# MCU.net
KiCad netlist of a schematic drawn in Altium Designer
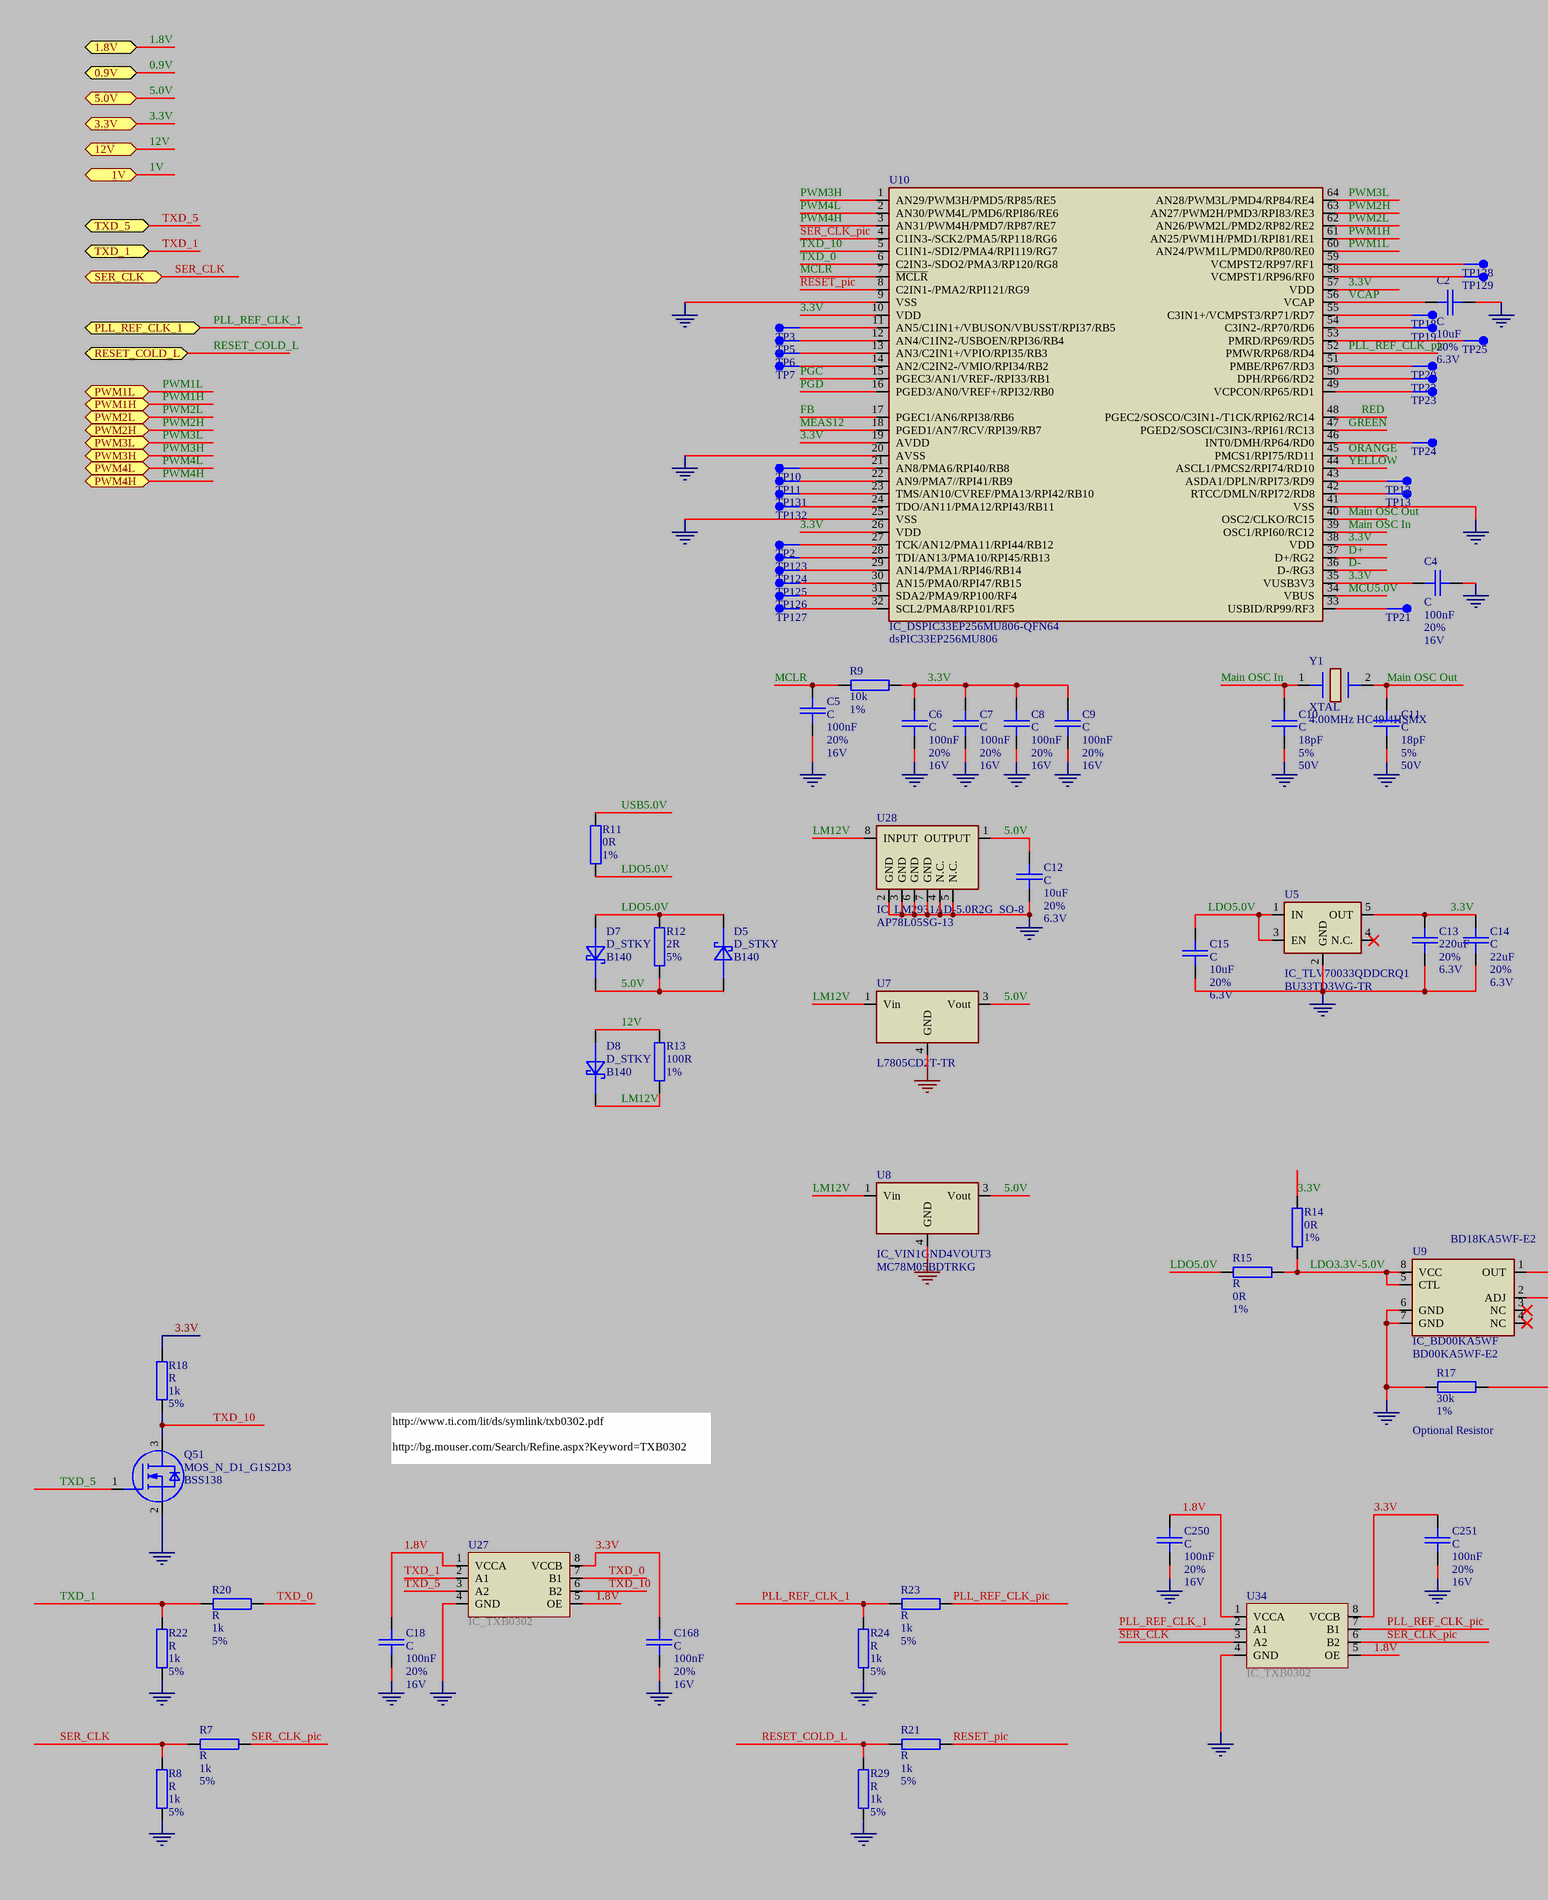
[diagram p0: MCU.SchDoc, left]
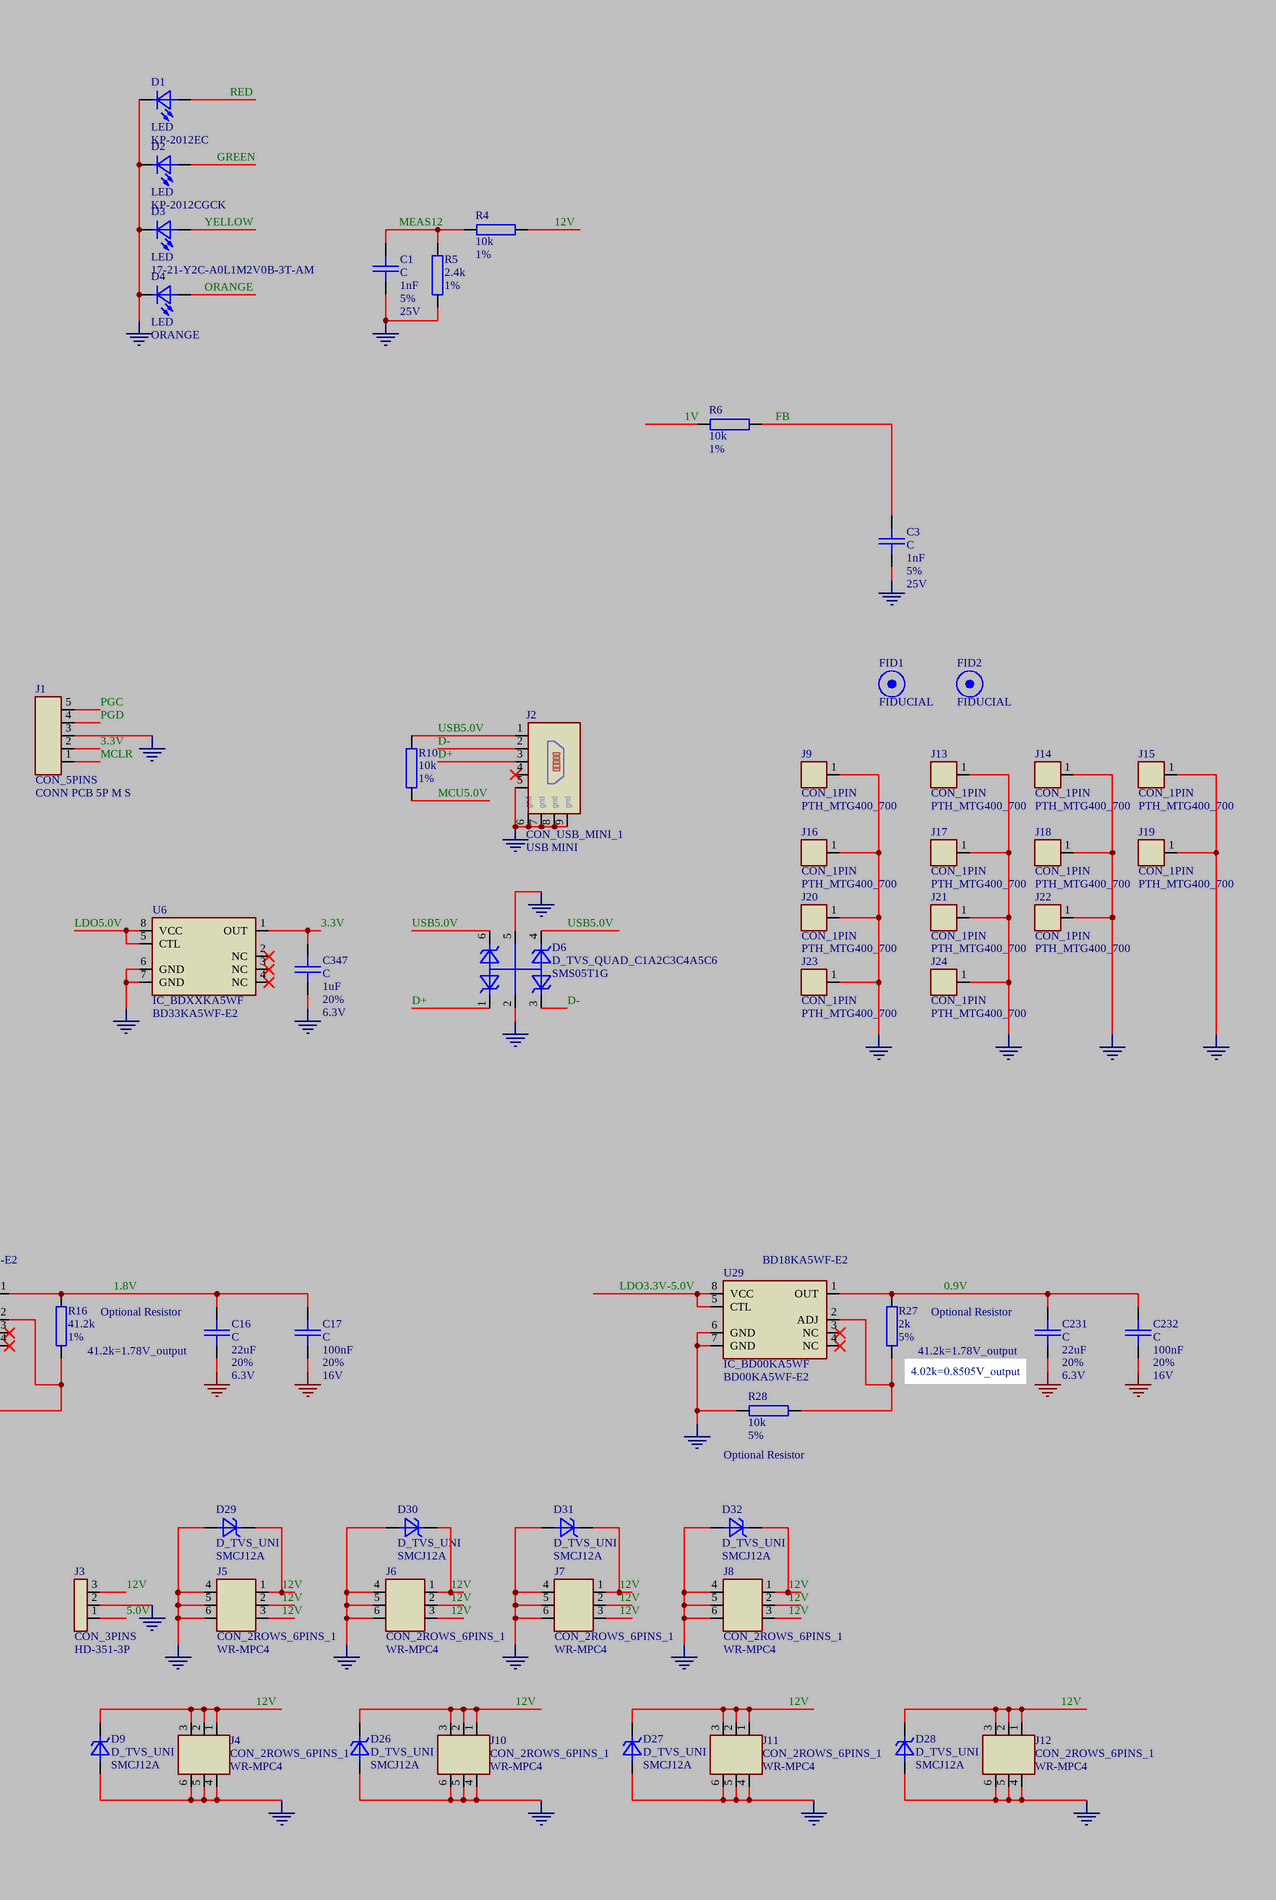
[diagram p1: MCU.SchDoc, right]

(export (version "E")
  (design (tool "Eeschema 10.0.6"))
  (components
    (comp (ref "C1")
      (value "C")
      (footprint "SMD_0603_CAPC1608X95N")
      (fields
        (field (name "DB_PART_NUMBER") "CAP000024113")
        (field (name "DB_VALUE") "1nF")
        (field (name "DB_TOLERANCE") "5%")
        (field (name "DB_VOLTAGE") "25V")
        (field (name "DB_MANUFACTURER_PART") "KEMET    C0603C102J3RAC")
      )
      (libsource (lib "Database_Libs1") (part "C"))
    )
    (comp (ref "C2")
      (value "C")
      (footprint "SMD_0603_CAPC1608X95N")
      (fields
        (field (name "DB_PART_NUMBER") "CAP000043646")
        (field (name "DB_VALUE") "10uF")
        (field (name "DB_TOLERANCE") "20%")
        (field (name "DB_VOLTAGE") "6.3V")
        (field (name "DB_MANUFACTURER_PART") "KEMET    C0603C106M9PAC")
      )
      (libsource (lib "Database_Libs1") (part "C"))
    )
    (comp (ref "C3")
      (value "C")
      (footprint "SMD_0603_CAPC1608X95N")
      (fields
        (field (name "DB_PART_NUMBER") "CAP000024113")
        (field (name "DB_VALUE") "1nF")
        (field (name "DB_TOLERANCE") "5%")
        (field (name "DB_VOLTAGE") "25V")
        (field (name "DB_MANUFACTURER_PART") "KEMET    C0603C102J3RAC")
      )
      (libsource (lib "Database_Libs1") (part "C"))
    )
    (comp (ref "C4")
      (value "C")
      (footprint "SMD_0402_CAPC1005X55N")
      (fields
        (field (name "DB_PART_NUMBER") "CAP000022751")
        (field (name "DB_VALUE") "100nF")
        (field (name "DB_TOLERANCE") "20%")
        (field (name "DB_VOLTAGE") "16V")
        (field (name "DB_MANUFACTURER_PART") "KEMET    C0402F104M4RAC")
      )
      (libsource (lib "Database_Libs1") (part "C"))
    )
    (comp (ref "C5")
      (value "C")
      (footprint "SMD_0402_CAPC1005X55N")
      (fields
        (field (name "DB_PART_NUMBER") "CAP000022751")
        (field (name "DB_VALUE") "100nF")
        (field (name "DB_TOLERANCE") "20%")
        (field (name "DB_VOLTAGE") "16V")
        (field (name "DB_MANUFACTURER_PART") "KEMET    C0402F104M4RAC")
      )
      (libsource (lib "Database_Libs1") (part "C"))
    )
    (comp (ref "C6")
      (value "C")
      (footprint "SMD_0402_CAPC1005X55N")
      (fields
        (field (name "DB_PART_NUMBER") "CAP000022751")
        (field (name "DB_VALUE") "100nF")
        (field (name "DB_TOLERANCE") "20%")
        (field (name "DB_VOLTAGE") "16V")
        (field (name "DB_MANUFACTURER_PART") "KEMET    C0402F104M4RAC")
      )
      (libsource (lib "Database_Libs1") (part "C"))
    )
    (comp (ref "C7")
      (value "C")
      (footprint "SMD_0402_CAPC1005X55N")
      (fields
        (field (name "DB_PART_NUMBER") "CAP000022751")
        (field (name "DB_VALUE") "100nF")
        (field (name "DB_TOLERANCE") "20%")
        (field (name "DB_VOLTAGE") "16V")
        (field (name "DB_MANUFACTURER_PART") "KEMET    C0402F104M4RAC")
      )
      (libsource (lib "Database_Libs1") (part "C"))
    )
    (comp (ref "C8")
      (value "C")
      (footprint "SMD_0402_CAPC1005X55N")
      (fields
        (field (name "DB_PART_NUMBER") "CAP000022751")
        (field (name "DB_VALUE") "100nF")
        (field (name "DB_TOLERANCE") "20%")
        (field (name "DB_VOLTAGE") "16V")
        (field (name "DB_MANUFACTURER_PART") "KEMET    C0402F104M4RAC")
      )
      (libsource (lib "Database_Libs1") (part "C"))
    )
    (comp (ref "C9")
      (value "C")
      (footprint "SMD_0402_CAPC1005X55N")
      (fields
        (field (name "DB_PART_NUMBER") "CAP000022751")
        (field (name "DB_VALUE") "100nF")
        (field (name "DB_TOLERANCE") "20%")
        (field (name "DB_VOLTAGE") "16V")
        (field (name "DB_MANUFACTURER_PART") "KEMET    C0402F104M4RAC")
      )
      (libsource (lib "Database_Libs1") (part "C"))
    )
    (comp (ref "C10")
      (value "C")
      (footprint "SMD_0603_CAPC1608X95N")
      (fields
        (field (name "DB_PART_NUMBER") "CAP000031922")
        (field (name "DB_VALUE") "18pF")
        (field (name "DB_TOLERANCE") "5%")
        (field (name "DB_VOLTAGE") "50V")
        (field (name "DB_MANUFACTURER_PART") "KEMET    C0603C180J5GAC")
      )
      (libsource (lib "Database_Libs1") (part "C"))
    )
    (comp (ref "C11")
      (value "C")
      (footprint "SMD_0603_CAPC1608X95N")
      (fields
        (field (name "DB_PART_NUMBER") "CAP000031922")
        (field (name "DB_VALUE") "18pF")
        (field (name "DB_TOLERANCE") "5%")
        (field (name "DB_VOLTAGE") "50V")
        (field (name "DB_MANUFACTURER_PART") "KEMET    C0603C180J5GAC")
      )
      (libsource (lib "Database_Libs1") (part "C"))
    )
    (comp (ref "C12")
      (value "C")
      (footprint "SMD_0603_CAPC1608X95N")
      (fields
        (field (name "DB_PART_NUMBER") "CAP000043646")
        (field (name "DB_VALUE") "10uF")
        (field (name "DB_TOLERANCE") "20%")
        (field (name "DB_VOLTAGE") "6.3V")
        (field (name "DB_MANUFACTURER_PART") "KEMET    C0603C106M9PAC")
      )
      (libsource (lib "Database_Libs1") (part "C"))
    )
    (comp (ref "C13")
      (value "C")
      (footprint "SMD_1210_CAPC3225X279N")
      (fields
        (field (name "DB_PART_NUMBER") "CAP000047355")
        (field (name "DB_VALUE") "220uF")
        (field (name "DB_TOLERANCE") "20%")
        (field (name "DB_VOLTAGE") "6.3V")
        (field (name "DB_MANUFACTURER_PART") "SAMSUNG    CL32A227MQVNNNE")
        (field (name "DB_APPROVED_BY") "VSN")
      )
      (libsource (lib "Database_Libs1") (part "C"))
    )
    (comp (ref "C14")
      (value "C")
      (footprint "SMD_0805_CAPC2012X145N")
      (fields
        (field (name "DB_PART_NUMBER") "CAP000043686")
        (field (name "DB_VALUE") "22uF")
        (field (name "DB_TOLERANCE") "20%")
        (field (name "DB_VOLTAGE") "6.3V")
        (field (name "DB_MANUFACTURER_PART") "KEMET    C0805C226M9PAC")
      )
      (libsource (lib "Database_Libs1") (part "C"))
    )
    (comp (ref "C15")
      (value "C")
      (footprint "SMD_0603_CAPC1608X95N")
      (fields
        (field (name "DB_PART_NUMBER") "CAP000043646")
        (field (name "DB_VALUE") "10uF")
        (field (name "DB_TOLERANCE") "20%")
        (field (name "DB_VOLTAGE") "6.3V")
        (field (name "DB_MANUFACTURER_PART") "KEMET    C0603C106M9PAC")
      )
      (libsource (lib "Database_Libs1") (part "C"))
    )
    (comp (ref "C16")
      (value "C")
      (footprint "SMD_0805_CAPC2012X145N")
      (fields
        (field (name "DB_PART_NUMBER") "CAP000043686")
        (field (name "DB_VALUE") "22uF")
        (field (name "DB_TOLERANCE") "20%")
        (field (name "DB_VOLTAGE") "6.3V")
        (field (name "DB_MANUFACTURER_PART") "KEMET    C0805C226M9PAC")
      )
      (libsource (lib "Database_Libs1") (part "C"))
    )
    (comp (ref "C17")
      (value "C")
      (footprint "SMD_0402_CAPC1005X55N")
      (fields
        (field (name "DB_PART_NUMBER") "CAP000022751")
        (field (name "DB_VALUE") "100nF")
        (field (name "DB_TOLERANCE") "20%")
        (field (name "DB_VOLTAGE") "16V")
        (field (name "DB_MANUFACTURER_PART") "KEMET    C0402F104M4RAC")
      )
      (libsource (lib "Database_Libs1") (part "C"))
    )
    (comp (ref "C18")
      (value "C")
      (footprint "SMD_0402_CAPC1005X55N")
      (fields
        (field (name "DB_PART_NUMBER") "CAP000022751")
        (field (name "DB_VALUE") "100nF")
        (field (name "DB_TOLERANCE") "20%")
        (field (name "DB_VOLTAGE") "16V")
        (field (name "DB_MANUFACTURER_PART") "KEMET    C0402F104M4RAC")
      )
      (libsource (lib "Database_Libs1") (part "C"))
    )
    (comp (ref "C168")
      (value "C")
      (footprint "SMD_0402_CAPC1005X55N")
      (fields
        (field (name "DB_PART_NUMBER") "CAP000022751")
        (field (name "DB_VALUE") "100nF")
        (field (name "DB_TOLERANCE") "20%")
        (field (name "DB_VOLTAGE") "16V")
        (field (name "DB_MANUFACTURER_PART") "KEMET    C0402F104M4RAC")
      )
      (libsource (lib "Database_Libs1") (part "C"))
    )
    (comp (ref "C231")
      (value "C")
      (footprint "SMD_0805_CAPC2012X145N")
      (fields
        (field (name "DB_PART_NUMBER") "CAP000043686")
        (field (name "DB_VALUE") "22uF")
        (field (name "DB_TOLERANCE") "20%")
        (field (name "DB_VOLTAGE") "6.3V")
        (field (name "DB_MANUFACTURER_PART") "KEMET    C0805C226M9PAC")
      )
      (libsource (lib "Database_Libs1") (part "C"))
    )
    (comp (ref "C232")
      (value "C")
      (footprint "SMD_0402_CAPC1005X55N")
      (fields
        (field (name "DB_PART_NUMBER") "CAP000022751")
        (field (name "DB_VALUE") "100nF")
        (field (name "DB_TOLERANCE") "20%")
        (field (name "DB_VOLTAGE") "16V")
        (field (name "DB_MANUFACTURER_PART") "KEMET    C0402F104M4RAC")
      )
      (libsource (lib "Database_Libs1") (part "C"))
    )
    (comp (ref "C250")
      (value "C")
      (footprint "SMD_0402_CAPC1005X55N")
      (fields
        (field (name "DB_PART_NUMBER") "CAP000022751")
        (field (name "DB_VALUE") "100nF")
        (field (name "DB_TOLERANCE") "20%")
        (field (name "DB_VOLTAGE") "16V")
        (field (name "DB_MANUFACTURER_PART") "KEMET    C0402F104M4RAC")
      )
      (libsource (lib "Database_Libs1") (part "C"))
    )
    (comp (ref "C251")
      (value "C")
      (footprint "SMD_0402_CAPC1005X55N")
      (fields
        (field (name "DB_PART_NUMBER") "CAP000022751")
        (field (name "DB_VALUE") "100nF")
        (field (name "DB_TOLERANCE") "20%")
        (field (name "DB_VOLTAGE") "16V")
        (field (name "DB_MANUFACTURER_PART") "KEMET    C0402F104M4RAC")
      )
      (libsource (lib "Database_Libs1") (part "C"))
    )
    (comp (ref "C347")
      (value "C")
      (footprint "SMD_0603_CAPC1608X95N")
      (fields
        (field (name "DB_PART_NUMBER") "CAP000043344")
        (field (name "DB_VALUE") "1uF")
        (field (name "DB_TOLERANCE") "20%")
        (field (name "DB_VOLTAGE") "6.3V")
        (field (name "DB_MANUFACTURER_PART") "KEMET    C0603C105M9PAC")
      )
      (libsource (lib "Database_Libs1") (part "C"))
    )
    (comp (ref "D1")
      (value "LED")
      (footprint "SMD_0805_LED2012X100N")
      (fields
        (field (name "DB_PART_NUMBER") "OPT000000095")
        (field (name "DB_VALUE") "KP-2012EC")
        (field (name "DB_MANUFACTURER_PART") "KINGBRIGHT       KP-2012EC")
        (field (name "DB_APPROVED_BY") "VSN")
      )
      (libsource (lib "Database_Libs1") (part "LED"))
    )
    (comp (ref "D2")
      (value "LED")
      (footprint "SMD_0805_LED2012X100N")
      (fields
        (field (name "DB_PART_NUMBER") "OPT000000096")
        (field (name "DB_VALUE") "KP-2012CGCK")
        (field (name "DB_MANUFACTURER_PART") "KINGBRIGHT       KP-2012CGCK")
        (field (name "DB_APPROVED_BY") "VSN")
      )
      (libsource (lib "Database_Libs1") (part "LED"))
    )
    (comp (ref "D3")
      (value "LED")
      (footprint "SMD_0805_LED2012X100N")
      (fields
        (field (name "DB_PART_NUMBER") "OPT000000092")
        (field (name "DB_VALUE") "17-21-Y2C-A0L1M2V0B-3T-AM")
        (field (name "DB_MANUFACTURER_PART") "EVERLIGHT       17-21-Y2C-A0L1M2V0B-3T-AM")
        (field (name "DB_APPROVED_BY") "VSN")
      )
      (libsource (lib "Database_Libs1") (part "LED"))
    )
    (comp (ref "D4")
      (value "LED")
      (footprint "SMD_0805_LED2012X100N")
      (fields
        (field (name "DB_PART_NUMBER") "OPT0000000zz")
        (field (name "DB_VALUE") "ORANGE")
        (field (name "DB_MANUFACTURER_PART") "KINGBRIGHT       ORANGE")
        (field (name "DB_APPROVED_BY") "VSN")
      )
      (libsource (lib "Database_Libs1") (part "LED"))
    )
    (comp (ref "D5")
      (value "D_STKY")
      (footprint "SMD_DO214AC_SMA")
      (fields
        (field (name "DB_PART_NUMBER") "DDE000000580")
        (field (name "DB_VALUE") "B140")
        (field (name "DB_MANUFACTURER_PART") "Diodes        B140")
      )
      (libsource (lib "Database_Libs1") (part "D_STKY"))
    )
    (comp (ref "D6")
      (value "D_TVS_QUAD_C1A2C3C4A5C6")
      (footprint "SMD_SOT457_SOT95P275X110-6N")
      (fields
        (field (name "DB_PART_NUMBER") "DDE000002846")
        (field (name "DB_VALUE") "SMS05T1G")
        (field (name "DB_MANUFACTURER_PART") "ON SEMICONDUCTOR        SMS05T1G")
        (field (name "DB_APPROVED_BY") "VSN")
      )
      (libsource (lib "Database_Libs1") (part "D_TVS_QUAD_C1A2C3C4A5C6"))
    )
    (comp (ref "D7")
      (value "D_STKY")
      (footprint "SMD_DO214AC_SMA")
      (fields
        (field (name "DB_PART_NUMBER") "DDE000000580")
        (field (name "DB_VALUE") "B140")
        (field (name "DB_MANUFACTURER_PART") "Diodes        B140")
      )
      (libsource (lib "Database_Libs1") (part "D_STKY"))
    )
    (comp (ref "D8")
      (value "D_STKY")
      (footprint "SMD_DO214AC_SMA")
      (fields
        (field (name "DB_PART_NUMBER") "DDE000000580")
        (field (name "DB_VALUE") "B140")
        (field (name "DB_MANUFACTURER_PART") "Diodes        B140")
      )
      (libsource (lib "Database_Libs1") (part "D_STKY"))
    )
    (comp (ref "D9")
      (value "D_TVS_UNI")
      (footprint "SMD_DO214AC_SMC")
      (fields
        (field (name "DB_PART_NUMBER") "DDE000001725")
        (field (name "DB_VALUE") "SMCJ12A")
        (field (name "DB_MANUFACTURER_PART") "Diodes        SMCJ12A")
      )
      (libsource (lib "Database_Libs1") (part "D_TVS_UNI"))
    )
    (comp (ref "D26")
      (value "D_TVS_UNI")
      (footprint "SMD_DO214AC_SMC")
      (fields
        (field (name "DB_PART_NUMBER") "DDE000001725")
        (field (name "DB_VALUE") "SMCJ12A")
        (field (name "DB_MANUFACTURER_PART") "Diodes        SMCJ12A")
      )
      (libsource (lib "Database_Libs1") (part "D_TVS_UNI"))
    )
    (comp (ref "D27")
      (value "D_TVS_UNI")
      (footprint "SMD_DO214AC_SMC")
      (fields
        (field (name "DB_PART_NUMBER") "DDE000001725")
        (field (name "DB_VALUE") "SMCJ12A")
        (field (name "DB_MANUFACTURER_PART") "Diodes        SMCJ12A")
      )
      (libsource (lib "Database_Libs1") (part "D_TVS_UNI"))
    )
    (comp (ref "D28")
      (value "D_TVS_UNI")
      (footprint "SMD_DO214AC_SMC")
      (fields
        (field (name "DB_PART_NUMBER") "DDE000001725")
        (field (name "DB_VALUE") "SMCJ12A")
        (field (name "DB_MANUFACTURER_PART") "Diodes        SMCJ12A")
      )
      (libsource (lib "Database_Libs1") (part "D_TVS_UNI"))
    )
    (comp (ref "D29")
      (value "D_TVS_UNI")
      (footprint "SMD_DO214AC_SMC")
      (fields
        (field (name "DB_PART_NUMBER") "DDE000001725")
        (field (name "DB_VALUE") "SMCJ12A")
        (field (name "DB_MANUFACTURER_PART") "Diodes        SMCJ12A")
      )
      (libsource (lib "Database_Libs1") (part "D_TVS_UNI"))
    )
    (comp (ref "D30")
      (value "D_TVS_UNI")
      (footprint "SMD_DO214AC_SMC")
      (fields
        (field (name "DB_PART_NUMBER") "DDE000001725")
        (field (name "DB_VALUE") "SMCJ12A")
        (field (name "DB_MANUFACTURER_PART") "Diodes        SMCJ12A")
      )
      (libsource (lib "Database_Libs1") (part "D_TVS_UNI"))
    )
    (comp (ref "D31")
      (value "D_TVS_UNI")
      (footprint "SMD_DO214AC_SMC")
      (fields
        (field (name "DB_PART_NUMBER") "DDE000001725")
        (field (name "DB_VALUE") "SMCJ12A")
        (field (name "DB_MANUFACTURER_PART") "Diodes        SMCJ12A")
      )
      (libsource (lib "Database_Libs1") (part "D_TVS_UNI"))
    )
    (comp (ref "D32")
      (value "D_TVS_UNI")
      (footprint "SMD_DO214AC_SMC")
      (fields
        (field (name "DB_PART_NUMBER") "DDE000001725")
        (field (name "DB_VALUE") "SMCJ12A")
        (field (name "DB_MANUFACTURER_PART") "Diodes        SMCJ12A")
      )
      (libsource (lib "Database_Libs1") (part "D_TVS_UNI"))
    )
    (comp (ref "FID1")
      (value "FIDUCIAL")
      (footprint "FID100X200")
      (fields
        (field (name "DB_PART_NUMBER") "FID000000001")
        (field (name "DB_MANUFACTURER_PART") "ISHIDDEN=T")
        (field (name "DB_APPROVED_BY") "ISHIDDEN=T")
      )
      (libsource (lib "Database_Libs1") (part "FIDUCIAL"))
    )
    (comp (ref "FID2")
      (value "FIDUCIAL")
      (footprint "FID100X200")
      (fields
        (field (name "DB_PART_NUMBER") "FID000000001")
        (field (name "DB_MANUFACTURER_PART") "ISHIDDEN=T")
        (field (name "DB_APPROVED_BY") "ISHIDDEN=T")
      )
      (libsource (lib "Database_Libs1") (part "FIDUCIAL"))
    )
    (comp (ref "J1")
      (value "CON_5PINS")
      (footprint "PTH_HDRV05W64P254_1X05")
      (fields
        (field (name "DB_PART_NUMBER") "CON000000006")
        (field (name "DB_VALUE") "CONN PCB 5P M S")
        (field (name "DB_MANUFACTURER_PART") "W+P        143-12-005-00")
        (field (name "DB_APPROVED_BY") "VSN")
      )
      (libsource (lib "Database_Libs1") (part "CON_5PINS"))
    )
    (comp (ref "J2")
      (value "CON_USB_MINI_1")
      (footprint "SMD_CON-CVILUX-CU04-SCM15B0")
      (fields
        (field (name "DB_PART_NUMBER") "CON000000048")
        (field (name "DB_VALUE") "USB MINI")
        (field (name "DB_MANUFACTURER_PART") "CVILUX       CU04-SCM15B0-R0-LF")
        (field (name "DB_APPROVED_BY") "VSN")
      )
      (libsource (lib "Database_Libs1") (part "CON_USB_MINI_1"))
    )
    (comp (ref "J3")
      (value "CON_3PINS")
      (footprint "PTH_CON_HD-351-3P")
      (fields
        (field (name "DB_PART_NUMBER") "CON000000272")
        (field (name "DB_VALUE") "HD-351-3P")
        (field (name "DB_MANUFACTURER_PART") "HOW DER      HD-351-3P")
        (field (name "DB_APPROVED_BY") "VSN")
      )
      (libsource (lib "Database_Libs1") (part "CON_3PINS"))
    )
    (comp (ref "J4")
      (value "CON_2ROWS_6PINS_1")
      (footprint "PTH_CON_WR-MRC4-6P_S")
      (fields
        (field (name "DB_PART_NUMBER") "CON000000279")
        (field (name "DB_VALUE") "WR-MPC4")
        (field (name "DB_MANUFACTURER_PART") "WE        	649 006 211 22")
        (field (name "DB_APPROVED_BY") "VSN")
      )
      (libsource (lib "Database_Libs1") (part "CON_2ROWS_6PINS_1"))
    )
    (comp (ref "J5")
      (value "CON_2ROWS_6PINS_1")
      (footprint "PTH_CON_WR-MRC4-6P_S")
      (fields
        (field (name "DB_PART_NUMBER") "CON000000279")
        (field (name "DB_VALUE") "WR-MPC4")
        (field (name "DB_MANUFACTURER_PART") "WE        	649 006 211 22")
        (field (name "DB_APPROVED_BY") "VSN")
      )
      (libsource (lib "Database_Libs1") (part "CON_2ROWS_6PINS_1"))
    )
    (comp (ref "J6")
      (value "CON_2ROWS_6PINS_1")
      (footprint "PTH_CON_WR-MRC4-6P_S")
      (fields
        (field (name "DB_PART_NUMBER") "CON000000279")
        (field (name "DB_VALUE") "WR-MPC4")
        (field (name "DB_MANUFACTURER_PART") "WE        	649 006 211 22")
        (field (name "DB_APPROVED_BY") "VSN")
      )
      (libsource (lib "Database_Libs1") (part "CON_2ROWS_6PINS_1"))
    )
    (comp (ref "J7")
      (value "CON_2ROWS_6PINS_1")
      (footprint "PTH_CON_WR-MRC4-6P_S")
      (fields
        (field (name "DB_PART_NUMBER") "CON000000279")
        (field (name "DB_VALUE") "WR-MPC4")
        (field (name "DB_MANUFACTURER_PART") "WE        	649 006 211 22")
        (field (name "DB_APPROVED_BY") "VSN")
      )
      (libsource (lib "Database_Libs1") (part "CON_2ROWS_6PINS_1"))
    )
    (comp (ref "J8")
      (value "CON_2ROWS_6PINS_1")
      (footprint "PTH_CON_WR-MRC4-6P_S")
      (fields
        (field (name "DB_PART_NUMBER") "CON000000279")
        (field (name "DB_VALUE") "WR-MPC4")
        (field (name "DB_MANUFACTURER_PART") "WE        	649 006 211 22")
        (field (name "DB_APPROVED_BY") "VSN")
      )
      (libsource (lib "Database_Libs1") (part "CON_2ROWS_6PINS_1"))
    )
    (comp (ref "J9")
      (value "CON_1PIN")
      (footprint "PTH_MTG400_700")
      (fields
        (field (name "DB_PART_NUMBER") "MTH000000030")
        (field (name "DB_VALUE") "PTH_MTG400_700")
        (field (name "DB_APPROVED_BY") "VSN")
      )
      (libsource (lib "Database_Libs1") (part "CON_1PIN"))
    )
    (comp (ref "J10")
      (value "CON_2ROWS_6PINS_1")
      (footprint "PTH_CON_WR-MRC4-6P_S")
      (fields
        (field (name "DB_PART_NUMBER") "CON000000279")
        (field (name "DB_VALUE") "WR-MPC4")
        (field (name "DB_MANUFACTURER_PART") "WE        	649 006 211 22")
        (field (name "DB_APPROVED_BY") "VSN")
      )
      (libsource (lib "Database_Libs1") (part "CON_2ROWS_6PINS_1"))
    )
    (comp (ref "J11")
      (value "CON_2ROWS_6PINS_1")
      (footprint "PTH_CON_WR-MRC4-6P_S")
      (fields
        (field (name "DB_PART_NUMBER") "CON000000279")
        (field (name "DB_VALUE") "WR-MPC4")
        (field (name "DB_MANUFACTURER_PART") "WE        	649 006 211 22")
        (field (name "DB_APPROVED_BY") "VSN")
      )
      (libsource (lib "Database_Libs1") (part "CON_2ROWS_6PINS_1"))
    )
    (comp (ref "J12")
      (value "CON_2ROWS_6PINS_1")
      (footprint "PTH_CON_WR-MRC4-6P_S")
      (fields
        (field (name "DB_PART_NUMBER") "CON000000279")
        (field (name "DB_VALUE") "WR-MPC4")
        (field (name "DB_MANUFACTURER_PART") "WE        	649 006 211 22")
        (field (name "DB_APPROVED_BY") "VSN")
      )
      (libsource (lib "Database_Libs1") (part "CON_2ROWS_6PINS_1"))
    )
    (comp (ref "J13")
      (value "CON_1PIN")
      (footprint "PTH_MTG400_700")
      (fields
        (field (name "DB_PART_NUMBER") "MTH000000030")
        (field (name "DB_VALUE") "PTH_MTG400_700")
        (field (name "DB_APPROVED_BY") "VSN")
      )
      (libsource (lib "Database_Libs1") (part "CON_1PIN"))
    )
    (comp (ref "J14")
      (value "CON_1PIN")
      (footprint "PTH_MTG400_700")
      (fields
        (field (name "DB_PART_NUMBER") "MTH000000030")
        (field (name "DB_VALUE") "PTH_MTG400_700")
        (field (name "DB_APPROVED_BY") "VSN")
      )
      (libsource (lib "Database_Libs1") (part "CON_1PIN"))
    )
    (comp (ref "J15")
      (value "CON_1PIN")
      (footprint "PTH_MTG400_700")
      (fields
        (field (name "DB_PART_NUMBER") "MTH000000030")
        (field (name "DB_VALUE") "PTH_MTG400_700")
        (field (name "DB_APPROVED_BY") "VSN")
      )
      (libsource (lib "Database_Libs1") (part "CON_1PIN"))
    )
    (comp (ref "J16")
      (value "CON_1PIN")
      (footprint "PTH_MTG400_700")
      (fields
        (field (name "DB_PART_NUMBER") "MTH000000030")
        (field (name "DB_VALUE") "PTH_MTG400_700")
        (field (name "DB_APPROVED_BY") "VSN")
      )
      (libsource (lib "Database_Libs1") (part "CON_1PIN"))
    )
    (comp (ref "J17")
      (value "CON_1PIN")
      (footprint "PTH_MTG400_700")
      (fields
        (field (name "DB_PART_NUMBER") "MTH000000030")
        (field (name "DB_VALUE") "PTH_MTG400_700")
        (field (name "DB_APPROVED_BY") "VSN")
      )
      (libsource (lib "Database_Libs1") (part "CON_1PIN"))
    )
    (comp (ref "J18")
      (value "CON_1PIN")
      (footprint "PTH_MTG400_700")
      (fields
        (field (name "DB_PART_NUMBER") "MTH000000030")
        (field (name "DB_VALUE") "PTH_MTG400_700")
        (field (name "DB_APPROVED_BY") "VSN")
      )
      (libsource (lib "Database_Libs1") (part "CON_1PIN"))
    )
    (comp (ref "J19")
      (value "CON_1PIN")
      (footprint "PTH_MTG400_700")
      (fields
        (field (name "DB_PART_NUMBER") "MTH000000030")
        (field (name "DB_VALUE") "PTH_MTG400_700")
        (field (name "DB_APPROVED_BY") "VSN")
      )
      (libsource (lib "Database_Libs1") (part "CON_1PIN"))
    )
    (comp (ref "J20")
      (value "CON_1PIN")
      (footprint "PTH_MTG400_700")
      (fields
        (field (name "DB_PART_NUMBER") "MTH000000030")
        (field (name "DB_VALUE") "PTH_MTG400_700")
        (field (name "DB_APPROVED_BY") "VSN")
      )
      (libsource (lib "Database_Libs1") (part "CON_1PIN"))
    )
    (comp (ref "J21")
      (value "CON_1PIN")
      (footprint "PTH_MTG400_700")
      (fields
        (field (name "DB_PART_NUMBER") "MTH000000030")
        (field (name "DB_VALUE") "PTH_MTG400_700")
        (field (name "DB_APPROVED_BY") "VSN")
      )
      (libsource (lib "Database_Libs1") (part "CON_1PIN"))
    )
    (comp (ref "J22")
      (value "CON_1PIN")
      (footprint "PTH_MTG400_700")
      (fields
        (field (name "DB_PART_NUMBER") "MTH000000030")
        (field (name "DB_VALUE") "PTH_MTG400_700")
        (field (name "DB_APPROVED_BY") "VSN")
      )
      (libsource (lib "Database_Libs1") (part "CON_1PIN"))
    )
    (comp (ref "J23")
      (value "CON_1PIN")
      (footprint "PTH_MTG400_700")
      (fields
        (field (name "DB_PART_NUMBER") "MTH000000030")
        (field (name "DB_VALUE") "PTH_MTG400_700")
        (field (name "DB_APPROVED_BY") "VSN")
      )
      (libsource (lib "Database_Libs1") (part "CON_1PIN"))
    )
    (comp (ref "J24")
      (value "CON_1PIN")
      (footprint "PTH_MTG400_700")
      (fields
        (field (name "DB_PART_NUMBER") "MTH000000030")
        (field (name "DB_VALUE") "PTH_MTG400_700")
        (field (name "DB_APPROVED_BY") "VSN")
      )
      (libsource (lib "Database_Libs1") (part "CON_1PIN"))
    )
    (comp (ref "Q51")
      (value "MOS_N_D1_G1S2D3")
      (footprint "SMD_SOT23_SOT95P240X112-3N")
      (fields
        (field (name "DB_PART_NUMBER") "TRA000001460")
        (field (name "DB_VALUE") "BSS138")
        (field (name "DB_MANUFACTURER_PART") "FAIRCHILD        BSS138LT1G")
        (field (name "DB_APPROVED_BY") "VSN")
      )
      (libsource (lib "Database_Libs1") (part "MOS_N_D1_G1S2D3"))
    )
    (comp (ref "R4")
      (value "R")
      (footprint "SMD_0603_RESC1608X55N")
      (fields
        (field (name "DB_PART_NUMBER") "RES000008663")
        (field (name "DB_VALUE") "10k")
        (field (name "DB_TOLERANCE") "1%")
        (field (name "DB_MANUFACTURER_PART") "YAGEO    RC0603FR-0710KL")
        (field (name "DB_APPROVED_BY") "VSN")
      )
      (libsource (lib "Database_Libs1") (part "R"))
    )
    (comp (ref "R5")
      (value "R")
      (footprint "SMD_0603_RESC1608X55N")
      (fields
        (field (name "DB_PART_NUMBER") "RES000006261")
        (field (name "DB_VALUE") "2.4k")
        (field (name "DB_TOLERANCE") "1%")
        (field (name "DB_MANUFACTURER_PART") "YAGEO    RC0603FR-072K4")
      )
      (libsource (lib "Database_Libs1") (part "R"))
    )
    (comp (ref "R6")
      (value "R")
      (footprint "SMD_0603_RESC1608X55N")
      (fields
        (field (name "DB_PART_NUMBER") "RES000008663")
        (field (name "DB_VALUE") "10k")
        (field (name "DB_TOLERANCE") "1%")
        (field (name "DB_MANUFACTURER_PART") "YAGEO    RC0603FR-0710KL")
        (field (name "DB_APPROVED_BY") "VSN")
      )
      (libsource (lib "Database_Libs1") (part "R"))
    )
    (comp (ref "R7")
      (value "R")
      (footprint "SMD_0603_RESC1608X55N")
      (fields
        (field (name "DB_PART_NUMBER") "RES000008858")
        (field (name "DB_VALUE") "1k")
        (field (name "DB_TOLERANCE") "5%")
        (field (name "DB_MANUFACTURER_PART") "YAGEO    AC0603JR-071KL")
        (field (name "DB_APPROVED_BY") "VSN")
      )
      (libsource (lib "Database_Libs1") (part "R"))
    )
    (comp (ref "R8")
      (value "R")
      (footprint "SMD_0603_RESC1608X55N")
      (fields
        (field (name "DB_PART_NUMBER") "RES000008858")
        (field (name "DB_VALUE") "1k")
        (field (name "DB_TOLERANCE") "5%")
        (field (name "DB_MANUFACTURER_PART") "YAGEO    AC0603JR-071KL")
        (field (name "DB_APPROVED_BY") "VSN")
      )
      (libsource (lib "Database_Libs1") (part "R"))
    )
    (comp (ref "R9")
      (value "R")
      (footprint "SMD_0603_RESC1608X55N")
      (fields
        (field (name "DB_PART_NUMBER") "RES000008663")
        (field (name "DB_VALUE") "10k")
        (field (name "DB_TOLERANCE") "1%")
        (field (name "DB_MANUFACTURER_PART") "YAGEO    RC0603FR-0710KL")
        (field (name "DB_APPROVED_BY") "VSN")
      )
      (libsource (lib "Database_Libs1") (part "R"))
    )
    (comp (ref "R10")
      (value "R")
      (footprint "SMD_0603_RESC1608X55N")
      (fields
        (field (name "DB_PART_NUMBER") "RES000008663")
        (field (name "DB_VALUE") "10k")
        (field (name "DB_TOLERANCE") "1%")
        (field (name "DB_MANUFACTURER_PART") "YAGEO    RC0603FR-0710KL")
        (field (name "DB_APPROVED_BY") "VSN")
      )
      (libsource (lib "Database_Libs1") (part "R"))
    )
    (comp (ref "R11")
      (value "R")
      (footprint "SMD_0603_RESC1608X55N")
      (fields
        (field (name "DB_PART_NUMBER") "RES000008926")
        (field (name "DB_VALUE") "0R")
        (field (name "DB_TOLERANCE") "1%")
        (field (name "DB_MANUFACTURER_PART") "YAGEO    AC0603FR-070RL")
        (field (name "DB_APPROVED_BY") "VSN")
      )
      (libsource (lib "Database_Libs1") (part "R"))
    )
    (comp (ref "R12")
      (value "R")
      (footprint "SMD_1206_RESC3216X65N")
      (fields
        (field (name "DB_PART_NUMBER") "RES000007051")
        (field (name "DB_VALUE") "2R")
        (field (name "DB_TOLERANCE") "5%")
        (field (name "DB_MANUFACTURER_PART") "YAGEO    RC1206JR-072R")
      )
      (libsource (lib "Database_Libs1") (part "R"))
    )
    (comp (ref "R13")
      (value "R")
      (footprint "SMD_1206_RESC3216X65N")
      (fields
        (field (name "DB_PART_NUMBER") "RES000006922")
        (field (name "DB_VALUE") "100R")
        (field (name "DB_TOLERANCE") "1%")
        (field (name "DB_MANUFACTURER_PART") "YAGEO    RC1206FR-07100R")
      )
      (libsource (lib "Database_Libs1") (part "R"))
    )
    (comp (ref "R14")
      (value "R")
      (footprint "SMD_1206_RESC3216X65N")
      (fields
        (field (name "DB_PART_NUMBER") "RES000008756")
        (field (name "DB_VALUE") "0R")
        (field (name "DB_TOLERANCE") "1%")
        (field (name "DB_MANUFACTURER_PART") "YAGEO    AC1206FR-070RL")
        (field (name "DB_APPROVED_BY") "VSN")
      )
      (libsource (lib "Database_Libs1") (part "R"))
    )
    (comp (ref "R15")
      (value "R")
      (footprint "SMD_1206_RESC3216X65N")
      (fields
        (field (name "DB_PART_NUMBER") "RES000008756")
        (field (name "DB_VALUE") "0R")
        (field (name "DB_TOLERANCE") "1%")
        (field (name "DB_MANUFACTURER_PART") "YAGEO    AC1206FR-070RL")
        (field (name "DB_APPROVED_BY") "VSN")
      )
      (libsource (lib "Database_Libs1") (part "R"))
    )
    (comp (ref "R16")
      (value "R")
      (footprint "SMD_0603_RESC1608X55N")
      (fields
        (field (name "DB_PART_NUMBER") "RES000001590")
        (field (name "DB_VALUE") "41.2k")
        (field (name "DB_TOLERANCE") "1%")
        (field (name "DB_MANUFACTURER_PART") "YAGEO    RC0603FR-0741K2")
      )
      (libsource (lib "Database_Libs1") (part "R"))
    )
    (comp (ref "R17")
      (value "R")
      (footprint "SMD_0603_RESC1608X55N")
      (fields
        (field (name "DB_PART_NUMBER") "RES000006287")
        (field (name "DB_VALUE") "30k")
        (field (name "DB_TOLERANCE") "1%")
        (field (name "DB_MANUFACTURER_PART") "YAGEO    RC0603FR-0730K")
      )
      (libsource (lib "Database_Libs1") (part "R"))
    )
    (comp (ref "R18")
      (value "R")
      (footprint "SMD_0603_RESC1608X55N")
      (fields
        (field (name "DB_PART_NUMBER") "RES000008858")
        (field (name "DB_VALUE") "1k")
        (field (name "DB_TOLERANCE") "5%")
        (field (name "DB_MANUFACTURER_PART") "YAGEO    AC0603JR-071KL")
        (field (name "DB_APPROVED_BY") "VSN")
      )
      (libsource (lib "Database_Libs1") (part "R"))
    )
    (comp (ref "R20")
      (value "R")
      (footprint "SMD_0603_RESC1608X55N")
      (fields
        (field (name "DB_PART_NUMBER") "RES000008858")
        (field (name "DB_VALUE") "1k")
        (field (name "DB_TOLERANCE") "5%")
        (field (name "DB_MANUFACTURER_PART") "YAGEO    AC0603JR-071KL")
        (field (name "DB_APPROVED_BY") "VSN")
      )
      (libsource (lib "Database_Libs1") (part "R"))
    )
    (comp (ref "R21")
      (value "R")
      (footprint "SMD_0603_RESC1608X55N")
      (fields
        (field (name "DB_PART_NUMBER") "RES000008858")
        (field (name "DB_VALUE") "1k")
        (field (name "DB_TOLERANCE") "5%")
        (field (name "DB_MANUFACTURER_PART") "YAGEO    AC0603JR-071KL")
        (field (name "DB_APPROVED_BY") "VSN")
      )
      (libsource (lib "Database_Libs1") (part "R"))
    )
    (comp (ref "R22")
      (value "R")
      (footprint "SMD_0603_RESC1608X55N")
      (fields
        (field (name "DB_PART_NUMBER") "RES000008858")
        (field (name "DB_VALUE") "1k")
        (field (name "DB_TOLERANCE") "5%")
        (field (name "DB_MANUFACTURER_PART") "YAGEO    AC0603JR-071KL")
        (field (name "DB_APPROVED_BY") "VSN")
      )
      (libsource (lib "Database_Libs1") (part "R"))
    )
    (comp (ref "R23")
      (value "R")
      (footprint "SMD_0603_RESC1608X55N")
      (fields
        (field (name "DB_PART_NUMBER") "RES000008858")
        (field (name "DB_VALUE") "1k")
        (field (name "DB_TOLERANCE") "5%")
        (field (name "DB_MANUFACTURER_PART") "YAGEO    AC0603JR-071KL")
        (field (name "DB_APPROVED_BY") "VSN")
      )
      (libsource (lib "Database_Libs1") (part "R"))
    )
    (comp (ref "R24")
      (value "R")
      (footprint "SMD_0603_RESC1608X55N")
      (fields
        (field (name "DB_PART_NUMBER") "RES000008858")
        (field (name "DB_VALUE") "1k")
        (field (name "DB_TOLERANCE") "5%")
        (field (name "DB_MANUFACTURER_PART") "YAGEO    AC0603JR-071KL")
        (field (name "DB_APPROVED_BY") "VSN")
      )
      (libsource (lib "Database_Libs1") (part "R"))
    )
    (comp (ref "R27")
      (value "R")
      (footprint "SMD_0603_RESC1608X55N")
      (fields
        (field (name "DB_PART_NUMBER") "RES000008857")
        (field (name "DB_VALUE") "2k")
        (field (name "DB_TOLERANCE") "5%")
        (field (name "DB_MANUFACTURER_PART") "YAGEO    AC0603JR-072KL")
        (field (name "DB_APPROVED_BY") "VSN")
      )
      (libsource (lib "Database_Libs1") (part "R"))
    )
    (comp (ref "R28")
      (value "R")
      (footprint "SMD_0603_RESC1608X55N")
      (fields
        (field (name "DB_PART_NUMBER") "RES000006446")
        (field (name "DB_VALUE") "10k")
        (field (name "DB_TOLERANCE") "5%")
        (field (name "DB_MANUFACTURER_PART") "YAGEO    RC0603JR-0710K")
      )
      (libsource (lib "Database_Libs1") (part "R"))
    )
    (comp (ref "R29")
      (value "R")
      (footprint "SMD_0603_RESC1608X55N")
      (fields
        (field (name "DB_PART_NUMBER") "RES000008858")
        (field (name "DB_VALUE") "1k")
        (field (name "DB_TOLERANCE") "5%")
        (field (name "DB_MANUFACTURER_PART") "YAGEO    AC0603JR-071KL")
        (field (name "DB_APPROVED_BY") "VSN")
      )
      (libsource (lib "Database_Libs1") (part "R"))
    )
    (comp (ref "TP2")
      (value "TEST_POINT_1")
      (footprint "SMD_TP_100-254")
      (fields (field (name "DB_PART_NUMBER") "TPO000000001"))
      (libsource (lib "Database_Libs1") (part "TEST_POINT_1"))
    )
    (comp (ref "TP3")
      (value "TEST_POINT_1")
      (footprint "SMD_TP_100-254")
      (fields (field (name "DB_PART_NUMBER") "TPO000000001"))
      (libsource (lib "Database_Libs1") (part "TEST_POINT_1"))
    )
    (comp (ref "TP5")
      (value "TEST_POINT_1")
      (footprint "SMD_TP_100-254")
      (fields (field (name "DB_PART_NUMBER") "TPO000000001"))
      (libsource (lib "Database_Libs1") (part "TEST_POINT_1"))
    )
    (comp (ref "TP6")
      (value "TEST_POINT_1")
      (footprint "SMD_TP_100-254")
      (fields (field (name "DB_PART_NUMBER") "TPO000000001"))
      (libsource (lib "Database_Libs1") (part "TEST_POINT_1"))
    )
    (comp (ref "TP7")
      (value "TEST_POINT_1")
      (footprint "SMD_TP_100-254")
      (fields (field (name "DB_PART_NUMBER") "TPO000000001"))
      (libsource (lib "Database_Libs1") (part "TEST_POINT_1"))
    )
    (comp (ref "TP10")
      (value "TEST_POINT_1")
      (footprint "SMD_TP_100-254")
      (fields (field (name "DB_PART_NUMBER") "TPO000000001"))
      (libsource (lib "Database_Libs1") (part "TEST_POINT_1"))
    )
    (comp (ref "TP11")
      (value "TEST_POINT_1")
      (footprint "SMD_TP_100-254")
      (fields (field (name "DB_PART_NUMBER") "TPO000000001"))
      (libsource (lib "Database_Libs1") (part "TEST_POINT_1"))
    )
    (comp (ref "TP12")
      (value "TEST_POINT_1")
      (footprint "SMD_TP_100-254")
      (fields (field (name "DB_PART_NUMBER") "TPO000000001"))
      (libsource (lib "Database_Libs1") (part "TEST_POINT_1"))
    )
    (comp (ref "TP13")
      (value "TEST_POINT_1")
      (footprint "SMD_TP_100-254")
      (fields (field (name "DB_PART_NUMBER") "TPO000000001"))
      (libsource (lib "Database_Libs1") (part "TEST_POINT_1"))
    )
    (comp (ref "TP18")
      (value "TEST_POINT_1")
      (footprint "SMD_TP_100-254")
      (fields (field (name "DB_PART_NUMBER") "TPO000000001"))
      (libsource (lib "Database_Libs1") (part "TEST_POINT_1"))
    )
    (comp (ref "TP19")
      (value "TEST_POINT_1")
      (footprint "SMD_TP_100-254")
      (fields (field (name "DB_PART_NUMBER") "TPO000000001"))
      (libsource (lib "Database_Libs1") (part "TEST_POINT_1"))
    )
    (comp (ref "TP20")
      (value "TEST_POINT_1")
      (footprint "SMD_TP_100-254")
      (fields (field (name "DB_PART_NUMBER") "TPO000000001"))
      (libsource (lib "Database_Libs1") (part "TEST_POINT_1"))
    )
    (comp (ref "TP21")
      (value "TEST_POINT_1")
      (footprint "SMD_TP_100-254")
      (fields (field (name "DB_PART_NUMBER") "TPO000000001"))
      (libsource (lib "Database_Libs1") (part "TEST_POINT_1"))
    )
    (comp (ref "TP22")
      (value "TEST_POINT_1")
      (footprint "SMD_TP_100-254")
      (fields (field (name "DB_PART_NUMBER") "TPO000000001"))
      (libsource (lib "Database_Libs1") (part "TEST_POINT_1"))
    )
    (comp (ref "TP23")
      (value "TEST_POINT_1")
      (footprint "SMD_TP_100-254")
      (fields (field (name "DB_PART_NUMBER") "TPO000000001"))
      (libsource (lib "Database_Libs1") (part "TEST_POINT_1"))
    )
    (comp (ref "TP24")
      (value "TEST_POINT_1")
      (footprint "SMD_TP_100-254")
      (fields (field (name "DB_PART_NUMBER") "TPO000000001"))
      (libsource (lib "Database_Libs1") (part "TEST_POINT_1"))
    )
    (comp (ref "TP25")
      (value "TEST_POINT_1")
      (footprint "SMD_TP_100-254")
      (fields (field (name "DB_PART_NUMBER") "TPO000000001"))
      (libsource (lib "Database_Libs1") (part "TEST_POINT_1"))
    )
    (comp (ref "TP123")
      (value "TEST_POINT_1")
      (footprint "SMD_TP_100-254")
      (fields (field (name "DB_PART_NUMBER") "TPO000000001"))
      (libsource (lib "Database_Libs1") (part "TEST_POINT_1"))
    )
    (comp (ref "TP124")
      (value "TEST_POINT_1")
      (footprint "SMD_TP_100-254")
      (fields (field (name "DB_PART_NUMBER") "TPO000000001"))
      (libsource (lib "Database_Libs1") (part "TEST_POINT_1"))
    )
    (comp (ref "TP125")
      (value "TEST_POINT_1")
      (footprint "SMD_TP_100-254")
      (fields (field (name "DB_PART_NUMBER") "TPO000000001"))
      (libsource (lib "Database_Libs1") (part "TEST_POINT_1"))
    )
    (comp (ref "TP126")
      (value "TEST_POINT_1")
      (footprint "SMD_TP_100-254")
      (fields (field (name "DB_PART_NUMBER") "TPO000000001"))
      (libsource (lib "Database_Libs1") (part "TEST_POINT_1"))
    )
    (comp (ref "TP127")
      (value "TEST_POINT_1")
      (footprint "SMD_TP_100-254")
      (fields (field (name "DB_PART_NUMBER") "TPO000000001"))
      (libsource (lib "Database_Libs1") (part "TEST_POINT_1"))
    )
    (comp (ref "TP128")
      (value "TEST_POINT_1")
      (footprint "SMD_TP_100-254")
      (fields (field (name "DB_PART_NUMBER") "TPO000000001"))
      (libsource (lib "Database_Libs1") (part "TEST_POINT_1"))
    )
    (comp (ref "TP129")
      (value "TEST_POINT_1")
      (footprint "SMD_TP_100-254")
      (fields (field (name "DB_PART_NUMBER") "TPO000000001"))
      (libsource (lib "Database_Libs1") (part "TEST_POINT_1"))
    )
    (comp (ref "TP131")
      (value "TEST_POINT_1")
      (footprint "SMD_TP_100-254")
      (fields (field (name "DB_PART_NUMBER") "TPO000000001"))
      (libsource (lib "Database_Libs1") (part "TEST_POINT_1"))
    )
    (comp (ref "TP132")
      (value "TEST_POINT_1")
      (footprint "SMD_TP_100-254")
      (fields (field (name "DB_PART_NUMBER") "TPO000000001"))
      (libsource (lib "Database_Libs1") (part "TEST_POINT_1"))
    )
    (comp (ref "U5")
      (value "IC_TLV70033QDDCRQ1")
      (footprint "SMD_SOT95P280X135-5N")
      (fields
        (field (name "DB_PART_NUMBER") "PSU000000126")
        (field (name "DB_VALUE") "BU33TD3WG-TR")
        (field (name "DB_MANUFACTURER_PART") "ROHM     BU33TD3WG-TR")
        (field (name "DB_APPROVED_BY") "VSN")
      )
      (libsource (lib "Database_Libs1") (part "IC_TLV70033QDDCRQ1"))
    )
    (comp (ref "U6")
      (value "IC_BDXXKA5WF")
      (footprint "SMD_SOIC127P620X160-8N")
      (fields
        (field (name "DB_PART_NUMBER") "PSU000000127")
        (field (name "DB_VALUE") "BD33KA5WF-E2")
        (field (name "DB_MANUFACTURER_PART") "ROHM        BD33KA5WF-E2")
        (field (name "DB_APPROVED_BY") "VSN")
      )
      (libsource (lib "Database_Libs1") (part "IC_BDXXKA5WF"))
    )
    (comp (ref "U7")
      (value "IC_IN1OUT3GND4")
      (footprint "SMD_TO254P1542X460-3_4N")
      (fields
        (field (name "DB_PART_NUMBER") "PSU000000129")
        (field (name "DB_VALUE") "L7805CD2T-TR")
        (field (name "DB_MANUFACTURER_PART") "ST       L7805CD2T-TR")
        (field (name "DB_APPROVED_BY") "VSN")
      )
      (libsource (lib "Database_Libs1") (part "IC_IN1OUT3GND4"))
    )
    (comp (ref "U8")
      (value "IC_VIN1GND4VOUT3")
      (footprint "SMD_TO229P991X239-4N_DPAK")
      (fields
        (field (name "DB_PART_NUMBER") "PSU000000031")
        (field (name "DB_VALUE") "MC78M05BDTRKG")
        (field (name "DB_MANUFACTURER_PART") "ON Semiconductor       MC78M05BDTRKG")
        (field (name "DB_APPROVED_BY") "VSN")
      )
      (libsource (lib "Database_Libs1") (part "IC_VIN1GND4VOUT3"))
    )
    (comp (ref "U9")
      (value "IC_BD00KA5WF")
      (footprint "SMD_SOIC127P620X160-8N")
      (fields
        (field (name "DB_PART_NUMBER") "PSU000000128")
        (field (name "DB_VALUE") "BD00KA5WF-E2")
        (field (name "DB_MANUFACTURER_PART") "ROHM        BD00KA5WF-E2")
        (field (name "DB_APPROVED_BY") "VSN")
      )
      (libsource (lib "Database_Libs1") (part "IC_BD00KA5WF"))
    )
    (comp (ref "U10")
      (value "IC_DSPIC33EP256MU806-QFN64")
      (footprint "SMD_QFP50P1200X1200X120-64N")
      (fields
        (field (name "DB_PART_NUMBER") "MCU000000070")
        (field (name "DB_VALUE") "dsPIC33EP256MU806")
        (field (name "DB_MANUFACTURER_PART") "MICROCHIP        DSPIC33EP256MU806-E/PT")
        (field (name "DB_APPROVED_BY") "VSN")
      )
      (libsource (lib "Database_Libs1") (part "IC_DSPIC33EP256MU806-QFN64"))
    )
    (comp (ref "U27")
      (value "IC_TXB0302")
      (footprint "SMD_PSON40P120X180X40-8N")
      (libsource (lib "Schlib1") (part "IC_TXB0302"))
    )
    (comp (ref "U28")
      (value "IC_LM2931AD-5.0R2G_SO-8")
      (footprint "SMD_SOIC127P600X175-8N")
      (fields
        (field (name "DB_PART_NUMBER") "PSU000000125")
        (field (name "DB_VALUE") "AP78L05SG-13")
        (field (name "DB_MANUFACTURER_PART") "DIODES        AP78L05SG-13")
        (field (name "DB_APPROVED_BY") "VSN")
      )
      (libsource (lib "Database_Libs1") (part "IC_LM2931AD-5.0R2G_SO-8"))
    )
    (comp (ref "U29")
      (value "IC_BD00KA5WF")
      (footprint "SMD_SOIC127P620X160-8N")
      (fields
        (field (name "DB_PART_NUMBER") "PSU000000128")
        (field (name "DB_VALUE") "BD00KA5WF-E2")
        (field (name "DB_MANUFACTURER_PART") "ROHM        BD00KA5WF-E2")
        (field (name "DB_APPROVED_BY") "VSN")
      )
      (libsource (lib "Database_Libs1") (part "IC_BD00KA5WF"))
    )
    (comp (ref "U34")
      (value "IC_TXB0302")
      (footprint "SMD_PSON40P120X180X40-8N")
      (libsource (lib "Schlib1") (part "IC_TXB0302"))
    )
    (comp (ref "Y1")
      (value "XTAL")
      (footprint "SMD_HC49_XTAL1140X480X420N")
      (fields
        (field (name "DB_PART_NUMBER") "OSC000000012")
        (field (name "DB_VALUE") "4.00MHz HC49/4HSMX")
        (field (name "DB_MANUFACTURER_PART") "IQD       4.00MHz HC49/4HSMX")
        (field (name "DB_APPROVED_BY") "VSN")
      )
      (libsource (lib "Database_Libs1") (part "XTAL"))
    )
  )
  (nets
    (net (code "1") (name "/0.9V") (class "Default")
      (node (ref "C231") (pin "1") (pinfunction "1_1") (pintype "passive"))
      (node (ref "C232") (pin "1") (pinfunction "1_1") (pintype "passive"))
      (node (ref "R27") (pin "1") (pinfunction "1_1") (pintype "passive"))
      (node (ref "U29") (pin "1") (pinfunction "OUT_1") (pintype "passive"))
    )
    (net (code "2") (name "/1.8V") (class "Default")
      (node (ref "C16") (pin "1") (pinfunction "1_1") (pintype "passive"))
      (node (ref "C17") (pin "1") (pinfunction "1_1") (pintype "passive"))
      (node (ref "C18") (pin "2") (pinfunction "2_2") (pintype "passive"))
      (node (ref "C250") (pin "2") (pinfunction "2_2") (pintype "passive"))
      (node (ref "R16") (pin "1") (pinfunction "1_1") (pintype "passive"))
      (node (ref "U27") (pin "1") (pinfunction "VCCA_1") (pintype "passive"))
      (node (ref "U27") (pin "5") (pinfunction "OE_5") (pintype "passive"))
      (node (ref "U34") (pin "1") (pinfunction "VCCA_1") (pintype "passive"))
      (node (ref "U34") (pin "5") (pinfunction "OE_5") (pintype "passive"))
      (node (ref "U9") (pin "1") (pinfunction "OUT_1") (pintype "passive"))
    )
    (net (code "3") (name "/1V") (class "Default")
      (node (ref "R6") (pin "2") (pinfunction "2_2") (pintype "passive"))
    )
    (net (code "4") (name "/3.3V") (class "Default")
      (node (ref "C13") (pin "2") (pinfunction "2_2") (pintype "passive"))
      (node (ref "C14") (pin "1") (pinfunction "1_1") (pintype "passive"))
      (node (ref "C168") (pin "2") (pinfunction "2_2") (pintype "passive"))
      (node (ref "C251") (pin "2") (pinfunction "2_2") (pintype "passive"))
      (node (ref "C347") (pin "1") (pinfunction "1_1") (pintype "passive"))
      (node (ref "C4") (pin "1") (pinfunction "1_1") (pintype "passive"))
      (node (ref "C6") (pin "1") (pinfunction "1_1") (pintype "passive"))
      (node (ref "C7") (pin "1") (pinfunction "1_1") (pintype "passive"))
      (node (ref "C8") (pin "1") (pinfunction "1_1") (pintype "passive"))
      (node (ref "C9") (pin "1") (pinfunction "1_1") (pintype "passive"))
      (node (ref "J1") (pin "2") (pinfunction "2_2") (pintype "passive"))
      (node (ref "R14") (pin "2") (pinfunction "2_2") (pintype "passive"))
      (node (ref "R18") (pin "1") (pinfunction "1_1") (pintype "passive"))
      (node (ref "R9") (pin "2") (pinfunction "2_2") (pintype "passive"))
      (node (ref "U10") (pin "10") (pinfunction "VDD_10") (pintype "passive"))
      (node (ref "U10") (pin "19") (pinfunction "AVDD_19") (pintype "passive"))
      (node (ref "U10") (pin "26") (pinfunction "VDD_26") (pintype "passive"))
      (node (ref "U10") (pin "35") (pinfunction "VUSB3V3_35") (pintype "passive"))
      (node (ref "U10") (pin "38") (pinfunction "VDD_38") (pintype "passive"))
      (node (ref "U10") (pin "57") (pinfunction "VDD_57") (pintype "passive"))
      (node (ref "U27") (pin "8") (pinfunction "VCCB_8") (pintype "passive"))
      (node (ref "U34") (pin "8") (pinfunction "VCCB_8") (pintype "passive"))
      (node (ref "U5") (pin "5") (pinfunction "OUT_5") (pintype "passive"))
      (node (ref "U6") (pin "1") (pinfunction "OUT_1") (pintype "passive"))
    )
    (net (code "5") (name "/5.0V") (class "Default")
      (node (ref "C12") (pin "1") (pinfunction "1_1") (pintype "passive"))
      (node (ref "D5") (pin "2") (pinfunction "A_2") (pintype "passive"))
      (node (ref "D7") (pin "1") (pinfunction "C_1") (pintype "passive"))
      (node (ref "J3") (pin "1") (pinfunction "1_1") (pintype "passive"))
      (node (ref "R12") (pin "1") (pinfunction "1_1") (pintype "passive"))
      (node (ref "U28") (pin "1") (pinfunction "OUTPUT_1") (pintype "passive"))
      (node (ref "U7") (pin "3") (pinfunction "Vout_3") (pintype "passive"))
      (node (ref "U8") (pin "3") (pinfunction "Vout_3") (pintype "passive"))
    )
    (net (code "6") (name "/12V") (class "Default")
      (node (ref "D26") (pin "1") (pinfunction "C_1") (pintype "passive"))
      (node (ref "D27") (pin "1") (pinfunction "C_1") (pintype "passive"))
      (node (ref "D28") (pin "1") (pinfunction "C_1") (pintype "passive"))
      (node (ref "D29") (pin "1") (pinfunction "C_1") (pintype "passive"))
      (node (ref "D30") (pin "1") (pinfunction "C_1") (pintype "passive"))
      (node (ref "D31") (pin "1") (pinfunction "C_1") (pintype "passive"))
      (node (ref "D32") (pin "1") (pinfunction "C_1") (pintype "passive"))
      (node (ref "D8") (pin "2") (pinfunction "A_2") (pintype "passive"))
      (node (ref "D9") (pin "1") (pinfunction "C_1") (pintype "passive"))
      (node (ref "J10") (pin "1") (pinfunction "1_1") (pintype "passive"))
      (node (ref "J10") (pin "2") (pinfunction "2_2") (pintype "passive"))
      (node (ref "J10") (pin "3") (pinfunction "3_3") (pintype "passive"))
      (node (ref "J11") (pin "1") (pinfunction "1_1") (pintype "passive"))
      (node (ref "J11") (pin "2") (pinfunction "2_2") (pintype "passive"))
      (node (ref "J11") (pin "3") (pinfunction "3_3") (pintype "passive"))
      (node (ref "J12") (pin "1") (pinfunction "1_1") (pintype "passive"))
      (node (ref "J12") (pin "2") (pinfunction "2_2") (pintype "passive"))
      (node (ref "J12") (pin "3") (pinfunction "3_3") (pintype "passive"))
      (node (ref "J3") (pin "3") (pinfunction "3_3") (pintype "passive"))
      (node (ref "J4") (pin "1") (pinfunction "1_1") (pintype "passive"))
      (node (ref "J4") (pin "2") (pinfunction "2_2") (pintype "passive"))
      (node (ref "J4") (pin "3") (pinfunction "3_3") (pintype "passive"))
      (node (ref "J5") (pin "1") (pinfunction "1_1") (pintype "passive"))
      (node (ref "J5") (pin "2") (pinfunction "2_2") (pintype "passive"))
      (node (ref "J5") (pin "3") (pinfunction "3_3") (pintype "passive"))
      (node (ref "J6") (pin "1") (pinfunction "1_1") (pintype "passive"))
      (node (ref "J6") (pin "2") (pinfunction "2_2") (pintype "passive"))
      (node (ref "J6") (pin "3") (pinfunction "3_3") (pintype "passive"))
      (node (ref "J7") (pin "1") (pinfunction "1_1") (pintype "passive"))
      (node (ref "J7") (pin "2") (pinfunction "2_2") (pintype "passive"))
      (node (ref "J7") (pin "3") (pinfunction "3_3") (pintype "passive"))
      (node (ref "J8") (pin "1") (pinfunction "1_1") (pintype "passive"))
      (node (ref "J8") (pin "2") (pinfunction "2_2") (pintype "passive"))
      (node (ref "J8") (pin "3") (pinfunction "3_3") (pintype "passive"))
      (node (ref "R13") (pin "2") (pinfunction "2_2") (pintype "passive"))
      (node (ref "R4") (pin "1") (pinfunction "1_1") (pintype "passive"))
    )
    (net (code "7") (name "/D+") (class "Default")
      (node (ref "D6") (pin "1") (pinfunction "1_1") (pintype "passive"))
      (node (ref "J2") (pin "3") (pinfunction "3_3") (pintype "passive"))
      (node (ref "U10") (pin "37") (pinfunction "D+/RG2_37") (pintype "passive"))
    )
    (net (code "8") (name "/D-") (class "Default")
      (node (ref "D6") (pin "3") (pinfunction "3_3") (pintype "passive"))
      (node (ref "J2") (pin "2") (pinfunction "2_2") (pintype "passive"))
      (node (ref "U10") (pin "36") (pinfunction "D-/RG3_36") (pintype "passive"))
    )
    (net (code "9") (name "/FB") (class "Default")
      (node (ref "C3") (pin "1") (pinfunction "1_1") (pintype "passive"))
      (node (ref "R6") (pin "1") (pinfunction "1_1") (pintype "passive"))
      (node (ref "U10") (pin "17") (pinfunction "PGEC1/AN6/RPI38/RB6_17") (pintype "passive"))
    )
    (net (code "10") (name "/GREEN") (class "Default")
      (node (ref "D2") (pin "2") (pinfunction "A_2") (pintype "passive"))
      (node (ref "U10") (pin "47") (pinfunction "PGED2/SOSCI/C3IN3-/RPI61/RC13_47") (pintype "passive"))
    )
    (net (code "11") (name "/LDO3.3V-5.0V") (class "Default")
      (node (ref "R14") (pin "1") (pinfunction "1_1") (pintype "passive"))
      (node (ref "R15") (pin "1") (pinfunction "1_1") (pintype "passive"))
      (node (ref "U29") (pin "5") (pinfunction "CTL_5") (pintype "passive"))
      (node (ref "U29") (pin "8") (pinfunction "VCC_8") (pintype "passive"))
      (node (ref "U9") (pin "5") (pinfunction "CTL_5") (pintype "passive"))
      (node (ref "U9") (pin "8") (pinfunction "VCC_8") (pintype "passive"))
    )
    (net (code "12") (name "/LDO5.0V") (class "Default")
      (node (ref "C15") (pin "1") (pinfunction "1_1") (pintype "passive"))
      (node (ref "D5") (pin "1") (pinfunction "C_1") (pintype "passive"))
      (node (ref "D7") (pin "2") (pinfunction "A_2") (pintype "passive"))
      (node (ref "R11") (pin "1") (pinfunction "1_1") (pintype "passive"))
      (node (ref "R12") (pin "2") (pinfunction "2_2") (pintype "passive"))
      (node (ref "R15") (pin "2") (pinfunction "2_2") (pintype "passive"))
      (node (ref "U5") (pin "1") (pinfunction "IN_1") (pintype "passive"))
      (node (ref "U5") (pin "3") (pinfunction "EN_3") (pintype "passive"))
      (node (ref "U6") (pin "5") (pinfunction "CTL_5") (pintype "passive"))
      (node (ref "U6") (pin "8") (pinfunction "VCC_8") (pintype "passive"))
    )
    (net (code "13") (name "/LM12V") (class "Default")
      (node (ref "D8") (pin "1") (pinfunction "C_1") (pintype "passive"))
      (node (ref "R13") (pin "1") (pinfunction "1_1") (pintype "passive"))
      (node (ref "U28") (pin "8") (pinfunction "INPUT_8") (pintype "passive"))
      (node (ref "U7") (pin "1") (pinfunction "Vin_1") (pintype "passive"))
      (node (ref "U8") (pin "1") (pinfunction "Vin_1") (pintype "passive"))
    )
    (net (code "14") (name "/MCLR") (class "Default")
      (node (ref "C5") (pin "1") (pinfunction "1_1") (pintype "passive"))
      (node (ref "J1") (pin "1") (pinfunction "1_1") (pintype "passive"))
      (node (ref "R9") (pin "1") (pinfunction "1_1") (pintype "passive"))
      (node (ref "U10") (pin "7") (pinfunction "~{MCLR}_7") (pintype "passive"))
    )
    (net (code "15") (name "/MCU5.0V") (class "Default")
      (node (ref "R10") (pin "2") (pinfunction "2_2") (pintype "passive"))
      (node (ref "U10") (pin "34") (pinfunction "VBUS_34") (pintype "passive"))
    )
    (net (code "16") (name "/MEAS12") (class "Default")
      (node (ref "C1") (pin "1") (pinfunction "1_1") (pintype "passive"))
      (node (ref "R4") (pin "2") (pinfunction "2_2") (pintype "passive"))
      (node (ref "R5") (pin "2") (pinfunction "2_2") (pintype "passive"))
      (node (ref "U10") (pin "18") (pinfunction "PGED1/AN7/RCV/RPI39/RB7_18") (pintype "passive"))
    )
    (net (code "17") (name "/Main OSC In") (class "Default")
      (node (ref "C10") (pin "1") (pinfunction "1_1") (pintype "passive"))
      (node (ref "U10") (pin "39") (pinfunction "OSC1/RPI60/RC12_39") (pintype "passive"))
      (node (ref "Y1") (pin "1") (pinfunction "1_1") (pintype "passive"))
    )
    (net (code "18") (name "/Main OSC Out") (class "Default")
      (node (ref "C11") (pin "1") (pinfunction "1_1") (pintype "passive"))
      (node (ref "U10") (pin "40") (pinfunction "OSC2/CLKO/RC15_40") (pintype "passive"))
      (node (ref "Y1") (pin "2") (pinfunction "2_2") (pintype "passive"))
    )
    (net (code "19") (name "/ORANGE") (class "Default")
      (node (ref "D4") (pin "2") (pinfunction "A_2") (pintype "passive"))
      (node (ref "U10") (pin "45") (pinfunction "PMCS1/RPI75/RD11_45") (pintype "passive"))
    )
    (net (code "20") (name "/PGC") (class "Default")
      (node (ref "J1") (pin "5") (pinfunction "5_5") (pintype "passive"))
      (node (ref "U10") (pin "15") (pinfunction "PGEC3/AN1/VREF-/RPI33/RB1_15") (pintype "passive"))
    )
    (net (code "21") (name "/PGD") (class "Default")
      (node (ref "J1") (pin "4") (pinfunction "4_4") (pintype "passive"))
      (node (ref "U10") (pin "16") (pinfunction "PGED3/AN0/VREF+/RPI32/RB0_16") (pintype "passive"))
    )
    (net (code "22") (name "/PLL_REF_CLK_1") (class "Default")
      (node (ref "R23") (pin "1") (pinfunction "1_1") (pintype "passive"))
      (node (ref "R24") (pin "1") (pinfunction "1_1") (pintype "passive"))
      (node (ref "U34") (pin "2") (pinfunction "A1_2") (pintype "passive"))
    )
    (net (code "23") (name "/PLL_REF_CLK_pic") (class "Default")
      (node (ref "R23") (pin "2") (pinfunction "2_2") (pintype "passive"))
      (node (ref "U10") (pin "52") (pinfunction "PMWR/RP68/RD4_52") (pintype "passive"))
      (node (ref "U34") (pin "7") (pinfunction "B1_7") (pintype "passive"))
    )
    (net (code "24") (name "/PWM1H") (class "Default")
      (node (ref "U10") (pin "61") (pinfunction "AN25/PWM1H/PMD1/RPI81/RE1_61") (pintype "passive"))
    )
    (net (code "25") (name "/PWM1L") (class "Default")
      (node (ref "U10") (pin "60") (pinfunction "AN24/PWM1L/PMD0/RP80/RE0_60") (pintype "passive"))
    )
    (net (code "26") (name "/PWM2H") (class "Default")
      (node (ref "U10") (pin "63") (pinfunction "AN27/PWM2H/PMD3/RPI83/RE3_63") (pintype "passive"))
    )
    (net (code "27") (name "/PWM2L") (class "Default")
      (node (ref "U10") (pin "62") (pinfunction "AN26/PWM2L/PMD2/RP82/RE2_62") (pintype "passive"))
    )
    (net (code "28") (name "/PWM3H") (class "Default")
      (node (ref "U10") (pin "1") (pinfunction "AN29/PWM3H/PMD5/RP85/RE5_1") (pintype "passive"))
    )
    (net (code "29") (name "/PWM3L") (class "Default")
      (node (ref "U10") (pin "64") (pinfunction "AN28/PWM3L/PMD4/RP84/RE4_64") (pintype "passive"))
    )
    (net (code "30") (name "/PWM4H") (class "Default")
      (node (ref "U10") (pin "3") (pinfunction "AN31/PWM4H/PMD7/RP87/RE7_3") (pintype "passive"))
    )
    (net (code "31") (name "/PWM4L") (class "Default")
      (node (ref "U10") (pin "2") (pinfunction "AN30/PWM4L/PMD6/RPI86/RE6_2") (pintype "passive"))
    )
    (net (code "32") (name "/RED") (class "Default")
      (node (ref "D1") (pin "2") (pinfunction "A_2") (pintype "passive"))
      (node (ref "U10") (pin "48") (pinfunction "PGEC2/SOSCO/C3IN1-/T1CK/RPI62/RC14_48") (pintype "passive"))
    )
    (net (code "33") (name "/RESET_COLD_L") (class "Default")
      (node (ref "R21") (pin "1") (pinfunction "1_1") (pintype "passive"))
      (node (ref "R29") (pin "1") (pinfunction "1_1") (pintype "passive"))
    )
    (net (code "34") (name "/RESET_pic") (class "Default")
      (node (ref "R21") (pin "2") (pinfunction "2_2") (pintype "passive"))
      (node (ref "U10") (pin "8") (pinfunction "C2IN1-/PMA2/RPI121/RG9_8") (pintype "passive"))
    )
    (net (code "35") (name "/SER_CLK") (class "Default")
      (node (ref "R7") (pin "1") (pinfunction "1_1") (pintype "passive"))
      (node (ref "R8") (pin "1") (pinfunction "1_1") (pintype "passive"))
      (node (ref "U34") (pin "3") (pinfunction "A2_3") (pintype "passive"))
    )
    (net (code "36") (name "/SER_CLK_pic") (class "Default")
      (node (ref "R7") (pin "2") (pinfunction "2_2") (pintype "passive"))
      (node (ref "U10") (pin "4") (pinfunction "C1IN3-/SCK2/PMA5/RP118/RG6_4") (pintype "passive"))
      (node (ref "U34") (pin "6") (pinfunction "B2_6") (pintype "passive"))
    )
    (net (code "37") (name "/TXD_0") (class "Default")
      (node (ref "R20") (pin "2") (pinfunction "2_2") (pintype "passive"))
      (node (ref "U10") (pin "6") (pinfunction "C2IN3-/SDO2/PMA3/RP120/RG8_6") (pintype "passive"))
      (node (ref "U27") (pin "7") (pinfunction "B1_7") (pintype "passive"))
    )
    (net (code "38") (name "/TXD_1") (class "Default")
      (node (ref "R20") (pin "1") (pinfunction "1_1") (pintype "passive"))
      (node (ref "R22") (pin "1") (pinfunction "1_1") (pintype "passive"))
      (node (ref "U27") (pin "2") (pinfunction "A1_2") (pintype "passive"))
    )
    (net (code "39") (name "/TXD_5") (class "Default")
      (node (ref "Q51") (pin "1") (pinfunction "G_1") (pintype "passive"))
      (node (ref "U27") (pin "3") (pinfunction "A2_3") (pintype "passive"))
    )
    (net (code "40") (name "/TXD_10") (class "Default")
      (node (ref "Q51") (pin "3") (pinfunction "D_3") (pintype "passive"))
      (node (ref "R18") (pin "2") (pinfunction "2_2") (pintype "passive"))
      (node (ref "U10") (pin "5") (pinfunction "C1IN1-/SDI2/PMA4/RPI119/RG7_5") (pintype "passive"))
      (node (ref "U27") (pin "6") (pinfunction "B2_6") (pintype "passive"))
    )
    (net (code "41") (name "/USB5.0V") (class "Default")
      (node (ref "D6") (pin "4") (pinfunction "4_4") (pintype "passive"))
      (node (ref "D6") (pin "6") (pinfunction "6_6") (pintype "passive"))
      (node (ref "J2") (pin "1") (pinfunction "1_1") (pintype "passive"))
      (node (ref "R10") (pin "1") (pinfunction "1_1") (pintype "passive"))
      (node (ref "R11") (pin "2") (pinfunction "2_2") (pintype "passive"))
    )
    (net (code "42") (name "/VCAP") (class "Default")
      (node (ref "C2") (pin "1") (pinfunction "1_1") (pintype "passive"))
      (node (ref "U10") (pin "56") (pinfunction "VCAP_56") (pintype "passive"))
    )
    (net (code "43") (name "/YELLOW") (class "Default")
      (node (ref "D3") (pin "2") (pinfunction "A_2") (pintype "passive"))
      (node (ref "U10") (pin "44") (pinfunction "ASCL1/PMCS2/RPI74/RD10_44") (pintype "passive"))
    )
    (net (code "44") (name "GND") (class "Default")
      (node (ref "C1") (pin "2") (pinfunction "2_2") (pintype "passive"))
      (node (ref "C10") (pin "2") (pinfunction "2_2") (pintype "passive"))
      (node (ref "C11") (pin "2") (pinfunction "2_2") (pintype "passive"))
      (node (ref "C12") (pin "2") (pinfunction "2_2") (pintype "passive"))
      (node (ref "C13") (pin "1") (pinfunction "1_1") (pintype "passive"))
      (node (ref "C14") (pin "2") (pinfunction "2_2") (pintype "passive"))
      (node (ref "C15") (pin "2") (pinfunction "2_2") (pintype "passive"))
      (node (ref "C16") (pin "2") (pinfunction "2_2") (pintype "passive"))
      (node (ref "C168") (pin "1") (pinfunction "1_1") (pintype "passive"))
      (node (ref "C17") (pin "2") (pinfunction "2_2") (pintype "passive"))
      (node (ref "C18") (pin "1") (pinfunction "1_1") (pintype "passive"))
      (node (ref "C2") (pin "2") (pinfunction "2_2") (pintype "passive"))
      (node (ref "C231") (pin "2") (pinfunction "2_2") (pintype "passive"))
      (node (ref "C232") (pin "2") (pinfunction "2_2") (pintype "passive"))
      (node (ref "C250") (pin "1") (pinfunction "1_1") (pintype "passive"))
      (node (ref "C251") (pin "1") (pinfunction "1_1") (pintype "passive"))
      (node (ref "C3") (pin "2") (pinfunction "2_2") (pintype "passive"))
      (node (ref "C347") (pin "2") (pinfunction "2_2") (pintype "passive"))
      (node (ref "C4") (pin "2") (pinfunction "2_2") (pintype "passive"))
      (node (ref "C5") (pin "2") (pinfunction "2_2") (pintype "passive"))
      (node (ref "C6") (pin "2") (pinfunction "2_2") (pintype "passive"))
      (node (ref "C7") (pin "2") (pinfunction "2_2") (pintype "passive"))
      (node (ref "C8") (pin "2") (pinfunction "2_2") (pintype "passive"))
      (node (ref "C9") (pin "2") (pinfunction "2_2") (pintype "passive"))
      (node (ref "D1") (pin "1") (pinfunction "C_1") (pintype "passive"))
      (node (ref "D2") (pin "1") (pinfunction "C_1") (pintype "passive"))
      (node (ref "D26") (pin "2") (pinfunction "A_2") (pintype "passive"))
      (node (ref "D27") (pin "2") (pinfunction "A_2") (pintype "passive"))
      (node (ref "D28") (pin "2") (pinfunction "A_2") (pintype "passive"))
      (node (ref "D29") (pin "2") (pinfunction "A_2") (pintype "passive"))
      (node (ref "D3") (pin "1") (pinfunction "C_1") (pintype "passive"))
      (node (ref "D30") (pin "2") (pinfunction "A_2") (pintype "passive"))
      (node (ref "D31") (pin "2") (pinfunction "A_2") (pintype "passive"))
      (node (ref "D32") (pin "2") (pinfunction "A_2") (pintype "passive"))
      (node (ref "D4") (pin "1") (pinfunction "C_1") (pintype "passive"))
      (node (ref "D6") (pin "2") (pinfunction "2_2") (pintype "passive"))
      (node (ref "D6") (pin "5") (pinfunction "5_5") (pintype "passive"))
      (node (ref "D9") (pin "2") (pinfunction "A_2") (pintype "passive"))
      (node (ref "J1") (pin "3") (pinfunction "3_3") (pintype "passive"))
      (node (ref "J10") (pin "4") (pinfunction "4_4") (pintype "passive"))
      (node (ref "J10") (pin "5") (pinfunction "5_5") (pintype "passive"))
      (node (ref "J10") (pin "6") (pinfunction "6_6") (pintype "passive"))
      (node (ref "J11") (pin "4") (pinfunction "4_4") (pintype "passive"))
      (node (ref "J11") (pin "5") (pinfunction "5_5") (pintype "passive"))
      (node (ref "J11") (pin "6") (pinfunction "6_6") (pintype "passive"))
      (node (ref "J12") (pin "4") (pinfunction "4_4") (pintype "passive"))
      (node (ref "J12") (pin "5") (pinfunction "5_5") (pintype "passive"))
      (node (ref "J12") (pin "6") (pinfunction "6_6") (pintype "passive"))
      (node (ref "J13") (pin "1") (pinfunction "1_1") (pintype "passive"))
      (node (ref "J14") (pin "1") (pinfunction "1_1") (pintype "passive"))
      (node (ref "J15") (pin "1") (pinfunction "1_1") (pintype "passive"))
      (node (ref "J16") (pin "1") (pinfunction "1_1") (pintype "passive"))
      (node (ref "J17") (pin "1") (pinfunction "1_1") (pintype "passive"))
      (node (ref "J18") (pin "1") (pinfunction "1_1") (pintype "passive"))
      (node (ref "J19") (pin "1") (pinfunction "1_1") (pintype "passive"))
      (node (ref "J2") (pin "5") (pinfunction "5_5") (pintype "passive"))
      (node (ref "J2") (pin "6") (pinfunction "6_6") (pintype "passive"))
      (node (ref "J2") (pin "7") (pinfunction "7_7") (pintype "passive"))
      (node (ref "J2") (pin "8") (pinfunction "8_8") (pintype "passive"))
      (node (ref "J2") (pin "9") (pinfunction "9_9") (pintype "passive"))
      (node (ref "J20") (pin "1") (pinfunction "1_1") (pintype "passive"))
      (node (ref "J21") (pin "1") (pinfunction "1_1") (pintype "passive"))
      (node (ref "J22") (pin "1") (pinfunction "1_1") (pintype "passive"))
      (node (ref "J23") (pin "1") (pinfunction "1_1") (pintype "passive"))
      (node (ref "J24") (pin "1") (pinfunction "1_1") (pintype "passive"))
      (node (ref "J3") (pin "2") (pinfunction "2_2") (pintype "passive"))
      (node (ref "J4") (pin "4") (pinfunction "4_4") (pintype "passive"))
      (node (ref "J4") (pin "5") (pinfunction "5_5") (pintype "passive"))
      (node (ref "J4") (pin "6") (pinfunction "6_6") (pintype "passive"))
      (node (ref "J5") (pin "4") (pinfunction "4_4") (pintype "passive"))
      (node (ref "J5") (pin "5") (pinfunction "5_5") (pintype "passive"))
      (node (ref "J5") (pin "6") (pinfunction "6_6") (pintype "passive"))
      (node (ref "J6") (pin "4") (pinfunction "4_4") (pintype "passive"))
      (node (ref "J6") (pin "5") (pinfunction "5_5") (pintype "passive"))
      (node (ref "J6") (pin "6") (pinfunction "6_6") (pintype "passive"))
      (node (ref "J7") (pin "4") (pinfunction "4_4") (pintype "passive"))
      (node (ref "J7") (pin "5") (pinfunction "5_5") (pintype "passive"))
      (node (ref "J7") (pin "6") (pinfunction "6_6") (pintype "passive"))
      (node (ref "J8") (pin "4") (pinfunction "4_4") (pintype "passive"))
      (node (ref "J8") (pin "5") (pinfunction "5_5") (pintype "passive"))
      (node (ref "J8") (pin "6") (pinfunction "6_6") (pintype "passive"))
      (node (ref "J9") (pin "1") (pinfunction "1_1") (pintype "passive"))
      (node (ref "Q51") (pin "2") (pinfunction "S_2") (pintype "passive"))
      (node (ref "R17") (pin "2") (pinfunction "2_2") (pintype "passive"))
      (node (ref "R22") (pin "2") (pinfunction "2_2") (pintype "passive"))
      (node (ref "R24") (pin "2") (pinfunction "2_2") (pintype "passive"))
      (node (ref "R28") (pin "2") (pinfunction "2_2") (pintype "passive"))
      (node (ref "R29") (pin "2") (pinfunction "2_2") (pintype "passive"))
      (node (ref "R5") (pin "1") (pinfunction "1_1") (pintype "passive"))
      (node (ref "R8") (pin "2") (pinfunction "2_2") (pintype "passive"))
      (node (ref "U10") (pin "20") (pinfunction "AVSS_20") (pintype "passive"))
      (node (ref "U10") (pin "25") (pinfunction "VSS_25") (pintype "passive"))
      (node (ref "U10") (pin "41") (pinfunction "VSS_41") (pintype "passive"))
      (node (ref "U10") (pin "9") (pinfunction "VSS_9") (pintype "passive"))
      (node (ref "U27") (pin "4") (pinfunction "GND_4") (pintype "passive"))
      (node (ref "U28") (pin "2") (pinfunction "GND_2") (pintype "passive"))
      (node (ref "U28") (pin "3") (pinfunction "GND_3") (pintype "passive"))
      (node (ref "U28") (pin "4") (pinfunction "N.C._4") (pintype "passive"))
      (node (ref "U28") (pin "5") (pinfunction "N.C._5") (pintype "passive"))
      (node (ref "U28") (pin "6") (pinfunction "GND_6") (pintype "passive"))
      (node (ref "U28") (pin "7") (pinfunction "GND_7") (pintype "passive"))
      (node (ref "U29") (pin "6") (pinfunction "GND_6") (pintype "passive"))
      (node (ref "U29") (pin "7") (pinfunction "GND_7") (pintype "passive"))
      (node (ref "U34") (pin "4") (pinfunction "GND_4") (pintype "passive"))
      (node (ref "U5") (pin "2") (pinfunction "GND_2") (pintype "passive"))
      (node (ref "U6") (pin "6") (pinfunction "GND_6") (pintype "passive"))
      (node (ref "U6") (pin "7") (pinfunction "GND_7") (pintype "passive"))
      (node (ref "U7") (pin "4") (pinfunction "GND_4") (pintype "passive"))
      (node (ref "U8") (pin "4") (pinfunction "GND_4") (pintype "passive"))
      (node (ref "U9") (pin "6") (pinfunction "GND_6") (pintype "passive"))
      (node (ref "U9") (pin "7") (pinfunction "GND_7") (pintype "passive"))
    )
    (net (code "45") (name "Net-(U9-ADJ)") (class "Default")
      (node (ref "R16") (pin "2") (pinfunction "2_2") (pintype "passive"))
      (node (ref "R17") (pin "1") (pinfunction "1_1") (pintype "passive"))
      (node (ref "U9") (pin "2") (pinfunction "ADJ_2") (pintype "passive"))
    )
    (net (code "46") (name "Net-(U10-AN2{slash}C2IN2-{slash}VMIO{slash}RPI34{slash}RB2)") (class "Default")
      (node (ref "TP7") (pin "1") (pinfunction "1_1") (pintype "passive"))
      (node (ref "U10") (pin "14") (pinfunction "AN2/C2IN2-/VMIO/RPI34/RB2_14") (pintype "passive"))
    )
    (net (code "47") (name "Net-(U10-AN3{slash}C2IN1+{slash}VPIO{slash}RPI35{slash}RB3)") (class "Default")
      (node (ref "TP6") (pin "1") (pinfunction "1_1") (pintype "passive"))
      (node (ref "U10") (pin "13") (pinfunction "AN3/C2IN1+/VPIO/RPI35/RB3_13") (pintype "passive"))
    )
    (net (code "48") (name "Net-(U10-AN4{slash}C1IN2-{slash}USBOEN{slash}RPI36{slash}RB4)") (class "Default")
      (node (ref "TP5") (pin "1") (pinfunction "1_1") (pintype "passive"))
      (node (ref "U10") (pin "12") (pinfunction "AN4/C1IN2-/USBOEN/RPI36/RB4_12") (pintype "passive"))
    )
    (net (code "49") (name "Net-(U10-AN5{slash}C1IN1+{slash}VBUSON{slash}VBUSST{slash}RPI37{slash}RB5)") (class "Default")
      (node (ref "TP3") (pin "1") (pinfunction "1_1") (pintype "passive"))
      (node (ref "U10") (pin "11") (pinfunction "AN5/C1IN1+/VBUSON/VBUSST/RPI37/RB5_11") (pintype "passive"))
    )
    (net (code "50") (name "Net-(U10-AN8{slash}PMA6{slash}RPI40{slash}RB8)") (class "Default")
      (node (ref "TP10") (pin "1") (pinfunction "1_1") (pintype "passive"))
      (node (ref "U10") (pin "21") (pinfunction "AN8/PMA6/RPI40/RB8_21") (pintype "passive"))
    )
    (net (code "51") (name "Net-(U10-AN9{slash}PMA7{slash}{slash}RPI41{slash}RB9)") (class "Default")
      (node (ref "TP11") (pin "1") (pinfunction "1_1") (pintype "passive"))
      (node (ref "U10") (pin "22") (pinfunction "AN9/PMA7//RPI41/RB9_22") (pintype "passive"))
    )
    (net (code "52") (name "Net-(U10-AN14{slash}PMA1{slash}RPI46{slash}RB14)") (class "Default")
      (node (ref "TP124") (pin "1") (pinfunction "1_1") (pintype "passive"))
      (node (ref "U10") (pin "29") (pinfunction "AN14/PMA1/RPI46/RB14_29") (pintype "passive"))
    )
    (net (code "53") (name "Net-(U10-AN15{slash}PMA0{slash}RPI47{slash}RB15)") (class "Default")
      (node (ref "TP125") (pin "1") (pinfunction "1_1") (pintype "passive"))
      (node (ref "U10") (pin "30") (pinfunction "AN15/PMA0/RPI47/RB15_30") (pintype "passive"))
    )
    (net (code "54") (name "Net-(U10-ASDA1{slash}DPLN{slash}RPI73{slash}RD9)") (class "Default")
      (node (ref "TP12") (pin "1") (pinfunction "1_1") (pintype "passive"))
      (node (ref "U10") (pin "43") (pinfunction "ASDA1/DPLN/RPI73/RD9_43") (pintype "passive"))
    )
    (net (code "55") (name "Net-(U10-C3IN1+{slash}VCMPST3{slash}RP71{slash}RD7)") (class "Default")
      (node (ref "TP18") (pin "1") (pinfunction "1_1") (pintype "passive"))
      (node (ref "U10") (pin "55") (pinfunction "C3IN1+/VCMPST3/RP71/RD7_55") (pintype "passive"))
    )
    (net (code "56") (name "Net-(U10-C3IN2-{slash}RP70{slash}RD6)") (class "Default")
      (node (ref "TP19") (pin "1") (pinfunction "1_1") (pintype "passive"))
      (node (ref "U10") (pin "54") (pinfunction "C3IN2-/RP70/RD6_54") (pintype "passive"))
    )
    (net (code "57") (name "Net-(U10-DPH{slash}RP66{slash}RD2)") (class "Default")
      (node (ref "TP22") (pin "1") (pinfunction "1_1") (pintype "passive"))
      (node (ref "U10") (pin "50") (pinfunction "DPH/RP66/RD2_50") (pintype "passive"))
    )
    (net (code "58") (name "Net-(U10-INT0{slash}DMH{slash}RP64{slash}RD0)") (class "Default")
      (node (ref "TP24") (pin "1") (pinfunction "1_1") (pintype "passive"))
      (node (ref "U10") (pin "46") (pinfunction "INT0/DMH/RP64/RD0_46") (pintype "passive"))
    )
    (net (code "59") (name "Net-(U10-PMBE{slash}RP67{slash}RD3)") (class "Default")
      (node (ref "TP20") (pin "1") (pinfunction "1_1") (pintype "passive"))
      (node (ref "U10") (pin "51") (pinfunction "PMBE/RP67/RD3_51") (pintype "passive"))
    )
    (net (code "60") (name "Net-(U10-PMRD{slash}RP69{slash}RD5)") (class "Default")
      (node (ref "TP25") (pin "1") (pinfunction "1_1") (pintype "passive"))
      (node (ref "U10") (pin "53") (pinfunction "PMRD/RP69/RD5_53") (pintype "passive"))
    )
    (net (code "61") (name "Net-(U10-RTCC{slash}DMLN{slash}RPI72{slash}RD8)") (class "Default")
      (node (ref "TP13") (pin "1") (pinfunction "1_1") (pintype "passive"))
      (node (ref "U10") (pin "42") (pinfunction "RTCC/DMLN/RPI72/RD8_42") (pintype "passive"))
    )
    (net (code "62") (name "Net-(U10-SCL2{slash}PMA8{slash}RP101{slash}RF5)") (class "Default")
      (node (ref "TP127") (pin "1") (pinfunction "1_1") (pintype "passive"))
      (node (ref "U10") (pin "32") (pinfunction "SCL2/PMA8/RP101/RF5_32") (pintype "passive"))
    )
    (net (code "63") (name "Net-(U10-SDA2{slash}PMA9{slash}RP100{slash}RF4)") (class "Default")
      (node (ref "TP126") (pin "1") (pinfunction "1_1") (pintype "passive"))
      (node (ref "U10") (pin "31") (pinfunction "SDA2/PMA9/RP100/RF4_31") (pintype "passive"))
    )
    (net (code "64") (name "Net-(U10-TCK{slash}AN12{slash}PMA11{slash}RPI44{slash}RB12)") (class "Default")
      (node (ref "TP2") (pin "1") (pinfunction "1_1") (pintype "passive"))
      (node (ref "U10") (pin "27") (pinfunction "TCK/AN12/PMA11/RPI44/RB12_27") (pintype "passive"))
    )
    (net (code "65") (name "Net-(U10-TDI{slash}AN13{slash}PMA10{slash}RPI45{slash}RB13)") (class "Default")
      (node (ref "TP123") (pin "1") (pinfunction "1_1") (pintype "passive"))
      (node (ref "U10") (pin "28") (pinfunction "TDI/AN13/PMA10/RPI45/RB13_28") (pintype "passive"))
    )
    (net (code "66") (name "Net-(U10-TDO{slash}AN11{slash}PMA12{slash}RPI43{slash}RB11)") (class "Default")
      (node (ref "TP132") (pin "1") (pinfunction "1_1") (pintype "passive"))
      (node (ref "U10") (pin "24") (pinfunction "TDO/AN11/PMA12/RPI43/RB11_24") (pintype "passive"))
    )
    (net (code "67") (name "Net-(U10-TMS{slash}AN10{slash}CVREF{slash}PMA13{slash}RPI42{slash}RB10)") (class "Default")
      (node (ref "TP131") (pin "1") (pinfunction "1_1") (pintype "passive"))
      (node (ref "U10") (pin "23") (pinfunction "TMS/AN10/CVREF/PMA13/RPI42/RB10_23") (pintype "passive"))
    )
    (net (code "68") (name "Net-(U10-USBID{slash}RP99{slash}RF3)") (class "Default")
      (node (ref "TP21") (pin "1") (pinfunction "1_1") (pintype "passive"))
      (node (ref "U10") (pin "33") (pinfunction "USBID/RP99/RF3_33") (pintype "passive"))
    )
    (net (code "69") (name "Net-(U10-VCMPST1{slash}RP96{slash}RF0)") (class "Default")
      (node (ref "TP129") (pin "1") (pinfunction "1_1") (pintype "passive"))
      (node (ref "U10") (pin "58") (pinfunction "VCMPST1/RP96/RF0_58") (pintype "passive"))
    )
    (net (code "70") (name "Net-(U10-VCMPST2{slash}RP97{slash}RF1)") (class "Default")
      (node (ref "TP128") (pin "1") (pinfunction "1_1") (pintype "passive"))
      (node (ref "U10") (pin "59") (pinfunction "VCMPST2/RP97/RF1_59") (pintype "passive"))
    )
    (net (code "71") (name "Net-(U10-VCPCON{slash}RP65{slash}RD1)") (class "Default")
      (node (ref "TP23") (pin "1") (pinfunction "1_1") (pintype "passive"))
      (node (ref "U10") (pin "49") (pinfunction "VCPCON/RP65/RD1_49") (pintype "passive"))
    )
    (net (code "72") (name "Net-(U29-ADJ)") (class "Default")
      (node (ref "R27") (pin "2") (pinfunction "2_2") (pintype "passive"))
      (node (ref "R28") (pin "1") (pinfunction "1_1") (pintype "passive"))
      (node (ref "U29") (pin "2") (pinfunction "ADJ_2") (pintype "passive"))
    )
    (net (code "73") (name "unconnected-(J2-Pad4)") (class "Default")
      (node (ref "J2") (pin "4") (pinfunction "4_4") (pintype "passive+no_connect"))
    )
    (net (code "74") (name "unconnected-(U5-N.C.-Pad4)") (class "Default")
      (node (ref "U5") (pin "4") (pinfunction "N.C._4") (pintype "passive+no_connect"))
    )
    (net (code "75") (name "unconnected-(U6-NC-Pad2)") (class "Default")
      (node (ref "U6") (pin "2") (pinfunction "NC_2") (pintype "passive+no_connect"))
    )
    (net (code "76") (name "unconnected-(U6-NC-Pad3)") (class "Default")
      (node (ref "U6") (pin "3") (pinfunction "NC_3") (pintype "passive+no_connect"))
    )
    (net (code "77") (name "unconnected-(U6-NC-Pad4)") (class "Default")
      (node (ref "U6") (pin "4") (pinfunction "NC_4") (pintype "passive+no_connect"))
    )
    (net (code "78") (name "unconnected-(U9-NC-Pad3)") (class "Default")
      (node (ref "U9") (pin "3") (pinfunction "NC_3") (pintype "passive+no_connect"))
    )
    (net (code "79") (name "unconnected-(U9-NC-Pad4)") (class "Default")
      (node (ref "U9") (pin "4") (pinfunction "NC_4") (pintype "passive+no_connect"))
    )
    (net (code "80") (name "unconnected-(U29-NC-Pad3)") (class "Default")
      (node (ref "U29") (pin "3") (pinfunction "NC_3") (pintype "passive+no_connect"))
    )
    (net (code "81") (name "unconnected-(U29-NC-Pad4)") (class "Default")
      (node (ref "U29") (pin "4") (pinfunction "NC_4") (pintype "passive+no_connect"))
    )
  )
)
